# 8iPanelLED.net
KiCad netlist of a schematic drawn in EAGLE
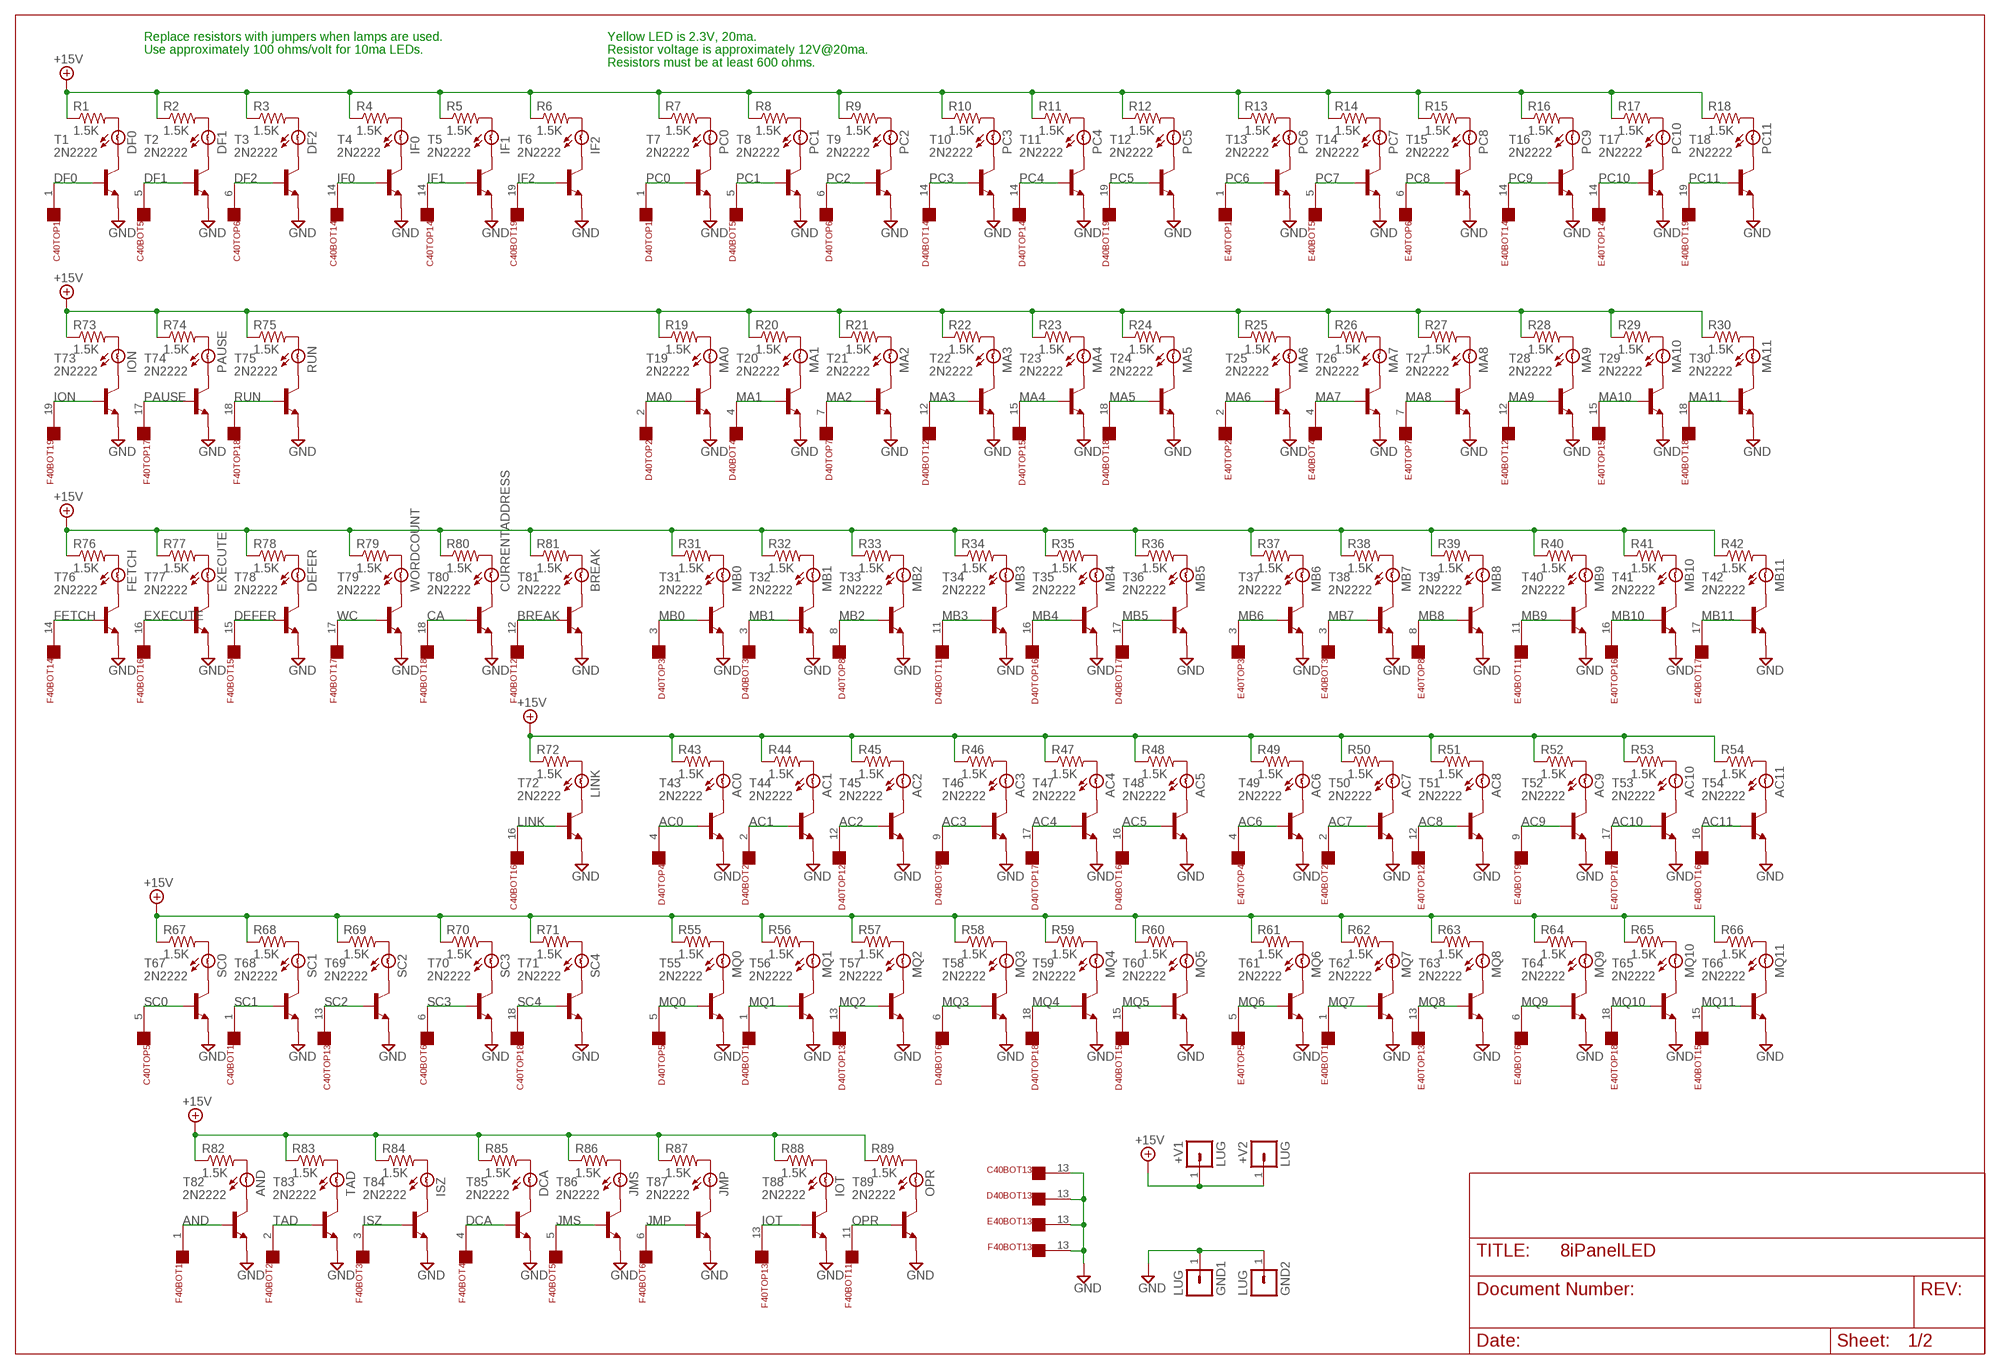
[diagram p0: schematic, sheet 1]
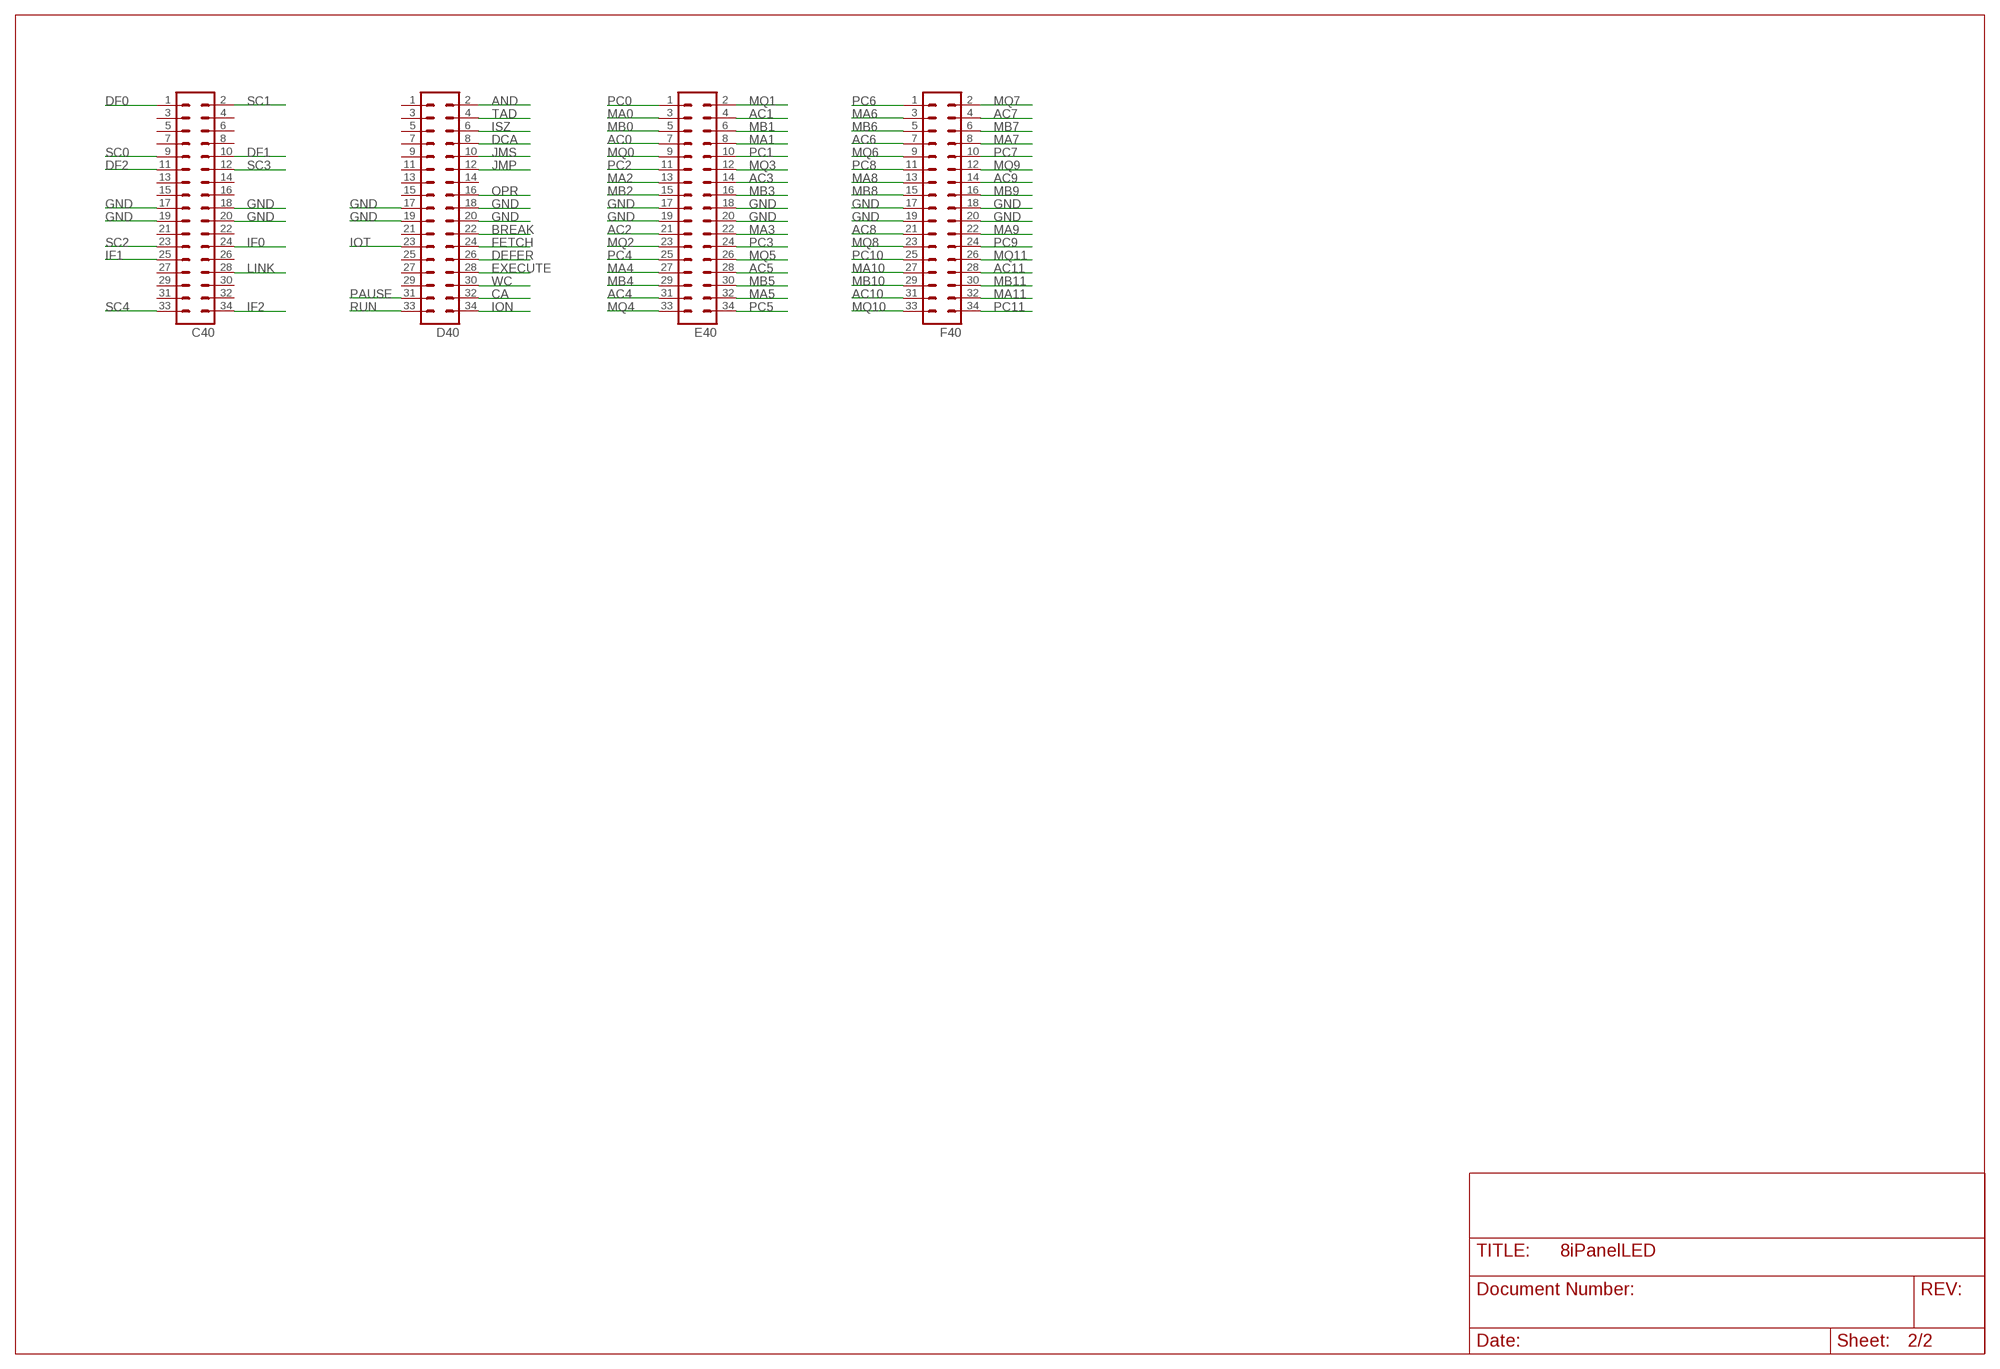
[diagram p1: schematic, sheet 2]

(export (version "E")
  (design (tool "Eeschema 10.0.6"))
  (components
    (comp (ref "C40")
      (value "MA17-2")
      (footprint "eagle-import:MA17-2")
      (libsource (lib "eagle-import") (part "MA17-2"))
    )
    (comp (ref "D40")
      (value "MA17-2")
      (footprint "eagle-import:MA17-2")
      (libsource (lib "eagle-import") (part "MA17-2"))
    )
    (comp (ref "E40")
      (value "MA17-2")
      (footprint "eagle-import:MA17-2")
      (libsource (lib "eagle-import") (part "MA17-2"))
    )
    (comp (ref "F40")
      (value "MA17-2")
      (footprint "eagle-import:MA17-2")
      (libsource (lib "eagle-import") (part "MA17-2"))
    )
    (comp (ref "+V1")
      (value "LUG")
      (footprint "eagle-import:SPADELUG")
      (libsource (lib "eagle-import") (part "LUG"))
    )
    (comp (ref "+V2")
      (value "LUG")
      (footprint "eagle-import:SPADELUG")
      (libsource (lib "eagle-import") (part "LUG"))
    )
    (comp (ref "AC0")
      (value "BULB")
      (footprint "eagle-import:BULB")
      (libsource (lib "eagle-import") (part "BULB"))
    )
    (comp (ref "AC1")
      (value "BULB")
      (footprint "eagle-import:BULB")
      (libsource (lib "eagle-import") (part "BULB"))
    )
    (comp (ref "AC2")
      (value "BULB")
      (footprint "eagle-import:BULB")
      (libsource (lib "eagle-import") (part "BULB"))
    )
    (comp (ref "AC3")
      (value "BULB")
      (footprint "eagle-import:BULB")
      (libsource (lib "eagle-import") (part "BULB"))
    )
    (comp (ref "AC4")
      (value "BULB")
      (footprint "eagle-import:BULB")
      (libsource (lib "eagle-import") (part "BULB"))
    )
    (comp (ref "AC5")
      (value "BULB")
      (footprint "eagle-import:BULB")
      (libsource (lib "eagle-import") (part "BULB"))
    )
    (comp (ref "AC6")
      (value "BULB")
      (footprint "eagle-import:BULB")
      (libsource (lib "eagle-import") (part "BULB"))
    )
    (comp (ref "AC7")
      (value "BULB")
      (footprint "eagle-import:BULB")
      (libsource (lib "eagle-import") (part "BULB"))
    )
    (comp (ref "AC8")
      (value "BULB")
      (footprint "eagle-import:BULB")
      (libsource (lib "eagle-import") (part "BULB"))
    )
    (comp (ref "AC9")
      (value "BULB")
      (footprint "eagle-import:BULB")
      (libsource (lib "eagle-import") (part "BULB"))
    )
    (comp (ref "AC10")
      (value "BULB")
      (footprint "eagle-import:BULB")
      (libsource (lib "eagle-import") (part "BULB"))
    )
    (comp (ref "AC11")
      (value "BULB")
      (footprint "eagle-import:BULB")
      (libsource (lib "eagle-import") (part "BULB"))
    )
    (comp (ref "AND")
      (value "BULB")
      (footprint "eagle-import:BULB")
      (libsource (lib "eagle-import") (part "BULB"))
    )
    (comp (ref "BREAK")
      (value "BULB")
      (footprint "eagle-import:BULB")
      (libsource (lib "eagle-import") (part "BULB"))
    )
    (comp (ref "C40BOT")
      (value "FLEX19")
      (footprint "eagle-import:FLEX19")
      (libsource (lib "eagle-import") (part "FLEX19"))
    )
    (comp (ref "C40TOP")
      (value "FLEX19")
      (footprint "eagle-import:FLEX19")
      (libsource (lib "eagle-import") (part "FLEX19"))
    )
    (comp (ref "CURRENTADDRESS")
      (value "BULB")
      (footprint "eagle-import:BULB")
      (libsource (lib "eagle-import") (part "BULB"))
    )
    (comp (ref "D40BOT")
      (value "FLEX19")
      (footprint "eagle-import:FLEX19")
      (libsource (lib "eagle-import") (part "FLEX19"))
    )
    (comp (ref "D40TOP")
      (value "FLEX19")
      (footprint "eagle-import:FLEX19")
      (libsource (lib "eagle-import") (part "FLEX19"))
    )
    (comp (ref "DCA")
      (value "BULB")
      (footprint "eagle-import:BULB")
      (libsource (lib "eagle-import") (part "BULB"))
    )
    (comp (ref "DEFER")
      (value "BULB")
      (footprint "eagle-import:BULB")
      (libsource (lib "eagle-import") (part "BULB"))
    )
    (comp (ref "DF0")
      (value "BULB")
      (footprint "eagle-import:BULB")
      (libsource (lib "eagle-import") (part "BULB"))
    )
    (comp (ref "DF1")
      (value "BULB")
      (footprint "eagle-import:BULB")
      (libsource (lib "eagle-import") (part "BULB"))
    )
    (comp (ref "DF2")
      (value "BULB")
      (footprint "eagle-import:BULB")
      (libsource (lib "eagle-import") (part "BULB"))
    )
    (comp (ref "E40BOT")
      (value "FLEX19")
      (footprint "eagle-import:FLEX19")
      (libsource (lib "eagle-import") (part "FLEX19"))
    )
    (comp (ref "E40TOP")
      (value "FLEX19")
      (footprint "eagle-import:FLEX19")
      (libsource (lib "eagle-import") (part "FLEX19"))
    )
    (comp (ref "EXECUTE")
      (value "BULB")
      (footprint "eagle-import:BULB")
      (libsource (lib "eagle-import") (part "BULB"))
    )
    (comp (ref "F40BOT")
      (value "FLEX19")
      (footprint "eagle-import:FLEX19")
      (libsource (lib "eagle-import") (part "FLEX19"))
    )
    (comp (ref "F40TOP")
      (value "FLEX19")
      (footprint "eagle-import:FLEX19")
      (libsource (lib "eagle-import") (part "FLEX19"))
    )
    (comp (ref "FETCH")
      (value "BULB")
      (footprint "eagle-import:BULB")
      (libsource (lib "eagle-import") (part "BULB"))
    )
    (comp (ref "GND1")
      (value "LUG")
      (footprint "eagle-import:SPADELUG")
      (libsource (lib "eagle-import") (part "LUG"))
    )
    (comp (ref "GND2")
      (value "LUG")
      (footprint "eagle-import:SPADELUG")
      (libsource (lib "eagle-import") (part "LUG"))
    )
    (comp (ref "IF0")
      (value "BULB")
      (footprint "eagle-import:BULB")
      (libsource (lib "eagle-import") (part "BULB"))
    )
    (comp (ref "IF1")
      (value "BULB")
      (footprint "eagle-import:BULB")
      (libsource (lib "eagle-import") (part "BULB"))
    )
    (comp (ref "IF2")
      (value "BULB")
      (footprint "eagle-import:BULB")
      (libsource (lib "eagle-import") (part "BULB"))
    )
    (comp (ref "ION")
      (value "BULB")
      (footprint "eagle-import:BULB")
      (libsource (lib "eagle-import") (part "BULB"))
    )
    (comp (ref "IOT")
      (value "BULB")
      (footprint "eagle-import:BULB")
      (libsource (lib "eagle-import") (part "BULB"))
    )
    (comp (ref "ISZ")
      (value "BULB")
      (footprint "eagle-import:BULB")
      (libsource (lib "eagle-import") (part "BULB"))
    )
    (comp (ref "JMP")
      (value "BULB")
      (footprint "eagle-import:BULB")
      (libsource (lib "eagle-import") (part "BULB"))
    )
    (comp (ref "JMS")
      (value "BULB")
      (footprint "eagle-import:BULB")
      (libsource (lib "eagle-import") (part "BULB"))
    )
    (comp (ref "LINK")
      (value "BULB")
      (footprint "eagle-import:BULB")
      (libsource (lib "eagle-import") (part "BULB"))
    )
    (comp (ref "MA0")
      (value "BULB")
      (footprint "eagle-import:BULB")
      (libsource (lib "eagle-import") (part "BULB"))
    )
    (comp (ref "MA1")
      (value "BULB")
      (footprint "eagle-import:BULB")
      (libsource (lib "eagle-import") (part "BULB"))
    )
    (comp (ref "MA2")
      (value "BULB")
      (footprint "eagle-import:BULB")
      (libsource (lib "eagle-import") (part "BULB"))
    )
    (comp (ref "MA3")
      (value "BULB")
      (footprint "eagle-import:BULB")
      (libsource (lib "eagle-import") (part "BULB"))
    )
    (comp (ref "MA4")
      (value "BULB")
      (footprint "eagle-import:BULB")
      (libsource (lib "eagle-import") (part "BULB"))
    )
    (comp (ref "MA5")
      (value "BULB")
      (footprint "eagle-import:BULB")
      (libsource (lib "eagle-import") (part "BULB"))
    )
    (comp (ref "MA6")
      (value "BULB")
      (footprint "eagle-import:BULB")
      (libsource (lib "eagle-import") (part "BULB"))
    )
    (comp (ref "MA7")
      (value "BULB")
      (footprint "eagle-import:BULB")
      (libsource (lib "eagle-import") (part "BULB"))
    )
    (comp (ref "MA8")
      (value "BULB")
      (footprint "eagle-import:BULB")
      (libsource (lib "eagle-import") (part "BULB"))
    )
    (comp (ref "MA9")
      (value "BULB")
      (footprint "eagle-import:BULB")
      (libsource (lib "eagle-import") (part "BULB"))
    )
    (comp (ref "MA10")
      (value "BULB")
      (footprint "eagle-import:BULB")
      (libsource (lib "eagle-import") (part "BULB"))
    )
    (comp (ref "MA11")
      (value "BULB")
      (footprint "eagle-import:BULB")
      (libsource (lib "eagle-import") (part "BULB"))
    )
    (comp (ref "MB0")
      (value "BULB")
      (footprint "eagle-import:BULB")
      (libsource (lib "eagle-import") (part "BULB"))
    )
    (comp (ref "MB1")
      (value "BULB")
      (footprint "eagle-import:BULB")
      (libsource (lib "eagle-import") (part "BULB"))
    )
    (comp (ref "MB2")
      (value "BULB")
      (footprint "eagle-import:BULB")
      (libsource (lib "eagle-import") (part "BULB"))
    )
    (comp (ref "MB3")
      (value "BULB")
      (footprint "eagle-import:BULB")
      (libsource (lib "eagle-import") (part "BULB"))
    )
    (comp (ref "MB4")
      (value "BULB")
      (footprint "eagle-import:BULB")
      (libsource (lib "eagle-import") (part "BULB"))
    )
    (comp (ref "MB5")
      (value "BULB")
      (footprint "eagle-import:BULB")
      (libsource (lib "eagle-import") (part "BULB"))
    )
    (comp (ref "MB6")
      (value "BULB")
      (footprint "eagle-import:BULB")
      (libsource (lib "eagle-import") (part "BULB"))
    )
    (comp (ref "MB7")
      (value "BULB")
      (footprint "eagle-import:BULB")
      (libsource (lib "eagle-import") (part "BULB"))
    )
    (comp (ref "MB8")
      (value "BULB")
      (footprint "eagle-import:BULB")
      (libsource (lib "eagle-import") (part "BULB"))
    )
    (comp (ref "MB9")
      (value "BULB")
      (footprint "eagle-import:BULB")
      (libsource (lib "eagle-import") (part "BULB"))
    )
    (comp (ref "MB10")
      (value "BULB")
      (footprint "eagle-import:BULB")
      (libsource (lib "eagle-import") (part "BULB"))
    )
    (comp (ref "MB11")
      (value "BULB")
      (footprint "eagle-import:BULB")
      (libsource (lib "eagle-import") (part "BULB"))
    )
    (comp (ref "MQ0")
      (value "BULB")
      (footprint "eagle-import:BULB")
      (libsource (lib "eagle-import") (part "BULB"))
    )
    (comp (ref "MQ1")
      (value "BULB")
      (footprint "eagle-import:BULB")
      (libsource (lib "eagle-import") (part "BULB"))
    )
    (comp (ref "MQ2")
      (value "BULB")
      (footprint "eagle-import:BULB")
      (libsource (lib "eagle-import") (part "BULB"))
    )
    (comp (ref "MQ3")
      (value "BULB")
      (footprint "eagle-import:BULB")
      (libsource (lib "eagle-import") (part "BULB"))
    )
    (comp (ref "MQ4")
      (value "BULB")
      (footprint "eagle-import:BULB")
      (libsource (lib "eagle-import") (part "BULB"))
    )
    (comp (ref "MQ5")
      (value "BULB")
      (footprint "eagle-import:BULB")
      (libsource (lib "eagle-import") (part "BULB"))
    )
    (comp (ref "MQ6")
      (value "BULB")
      (footprint "eagle-import:BULB")
      (libsource (lib "eagle-import") (part "BULB"))
    )
    (comp (ref "MQ7")
      (value "BULB")
      (footprint "eagle-import:BULB")
      (libsource (lib "eagle-import") (part "BULB"))
    )
    (comp (ref "MQ8")
      (value "BULB")
      (footprint "eagle-import:BULB")
      (libsource (lib "eagle-import") (part "BULB"))
    )
    (comp (ref "MQ9")
      (value "BULB")
      (footprint "eagle-import:BULB")
      (libsource (lib "eagle-import") (part "BULB"))
    )
    (comp (ref "MQ10")
      (value "BULB")
      (footprint "eagle-import:BULB")
      (libsource (lib "eagle-import") (part "BULB"))
    )
    (comp (ref "MQ11")
      (value "BULB")
      (footprint "eagle-import:BULB")
      (libsource (lib "eagle-import") (part "BULB"))
    )
    (comp (ref "OPR")
      (value "BULB")
      (footprint "eagle-import:BULB")
      (libsource (lib "eagle-import") (part "BULB"))
    )
    (comp (ref "PAUSE")
      (value "BULB")
      (footprint "eagle-import:BULB")
      (libsource (lib "eagle-import") (part "BULB"))
    )
    (comp (ref "PC0")
      (value "BULB")
      (footprint "eagle-import:BULB")
      (libsource (lib "eagle-import") (part "BULB"))
    )
    (comp (ref "PC1")
      (value "BULB")
      (footprint "eagle-import:BULB")
      (libsource (lib "eagle-import") (part "BULB"))
    )
    (comp (ref "PC2")
      (value "BULB")
      (footprint "eagle-import:BULB")
      (libsource (lib "eagle-import") (part "BULB"))
    )
    (comp (ref "PC3")
      (value "BULB")
      (footprint "eagle-import:BULB")
      (libsource (lib "eagle-import") (part "BULB"))
    )
    (comp (ref "PC4")
      (value "BULB")
      (footprint "eagle-import:BULB")
      (libsource (lib "eagle-import") (part "BULB"))
    )
    (comp (ref "PC5")
      (value "BULB")
      (footprint "eagle-import:BULB")
      (libsource (lib "eagle-import") (part "BULB"))
    )
    (comp (ref "PC6")
      (value "BULB")
      (footprint "eagle-import:BULB")
      (libsource (lib "eagle-import") (part "BULB"))
    )
    (comp (ref "PC7")
      (value "BULB")
      (footprint "eagle-import:BULB")
      (libsource (lib "eagle-import") (part "BULB"))
    )
    (comp (ref "PC8")
      (value "BULB")
      (footprint "eagle-import:BULB")
      (libsource (lib "eagle-import") (part "BULB"))
    )
    (comp (ref "PC9")
      (value "BULB")
      (footprint "eagle-import:BULB")
      (libsource (lib "eagle-import") (part "BULB"))
    )
    (comp (ref "PC10")
      (value "BULB")
      (footprint "eagle-import:BULB")
      (libsource (lib "eagle-import") (part "BULB"))
    )
    (comp (ref "PC11")
      (value "BULB")
      (footprint "eagle-import:BULB")
      (libsource (lib "eagle-import") (part "BULB"))
    )
    (comp (ref "R1")
      (value "1.5K")
      (footprint "eagle-import:0207_10")
      (libsource (lib "eagle-import") (part "R-US_0207/10"))
    )
    (comp (ref "R2")
      (value "1.5K")
      (footprint "eagle-import:0207_10")
      (libsource (lib "eagle-import") (part "R-US_0207/10"))
    )
    (comp (ref "R3")
      (value "1.5K")
      (footprint "eagle-import:0207_10")
      (libsource (lib "eagle-import") (part "R-US_0207/10"))
    )
    (comp (ref "R4")
      (value "1.5K")
      (footprint "eagle-import:0207_10")
      (libsource (lib "eagle-import") (part "R-US_0207/10"))
    )
    (comp (ref "R5")
      (value "1.5K")
      (footprint "eagle-import:0207_10")
      (libsource (lib "eagle-import") (part "R-US_0207/10"))
    )
    (comp (ref "R6")
      (value "1.5K")
      (footprint "eagle-import:0207_10")
      (libsource (lib "eagle-import") (part "R-US_0207/10"))
    )
    (comp (ref "R7")
      (value "1.5K")
      (footprint "eagle-import:0207_10")
      (libsource (lib "eagle-import") (part "R-US_0207/10"))
    )
    (comp (ref "R8")
      (value "1.5K")
      (footprint "eagle-import:0207_10")
      (libsource (lib "eagle-import") (part "R-US_0207/10"))
    )
    (comp (ref "R9")
      (value "1.5K")
      (footprint "eagle-import:0207_10")
      (libsource (lib "eagle-import") (part "R-US_0207/10"))
    )
    (comp (ref "R10")
      (value "1.5K")
      (footprint "eagle-import:0207_10")
      (libsource (lib "eagle-import") (part "R-US_0207/10"))
    )
    (comp (ref "R11")
      (value "1.5K")
      (footprint "eagle-import:0207_10")
      (libsource (lib "eagle-import") (part "R-US_0207/10"))
    )
    (comp (ref "R12")
      (value "1.5K")
      (footprint "eagle-import:0207_10")
      (libsource (lib "eagle-import") (part "R-US_0207/10"))
    )
    (comp (ref "R13")
      (value "1.5K")
      (footprint "eagle-import:0207_10")
      (libsource (lib "eagle-import") (part "R-US_0207/10"))
    )
    (comp (ref "R14")
      (value "1.5K")
      (footprint "eagle-import:0207_10")
      (libsource (lib "eagle-import") (part "R-US_0207/10"))
    )
    (comp (ref "R15")
      (value "1.5K")
      (footprint "eagle-import:0207_10")
      (libsource (lib "eagle-import") (part "R-US_0207/10"))
    )
    (comp (ref "R16")
      (value "1.5K")
      (footprint "eagle-import:0207_10")
      (libsource (lib "eagle-import") (part "R-US_0207/10"))
    )
    (comp (ref "R17")
      (value "1.5K")
      (footprint "eagle-import:0207_10")
      (libsource (lib "eagle-import") (part "R-US_0207/10"))
    )
    (comp (ref "R18")
      (value "1.5K")
      (footprint "eagle-import:0207_10")
      (libsource (lib "eagle-import") (part "R-US_0207/10"))
    )
    (comp (ref "R19")
      (value "1.5K")
      (footprint "eagle-import:0207_10")
      (libsource (lib "eagle-import") (part "R-US_0207/10"))
    )
    (comp (ref "R20")
      (value "1.5K")
      (footprint "eagle-import:0207_10")
      (libsource (lib "eagle-import") (part "R-US_0207/10"))
    )
    (comp (ref "R21")
      (value "1.5K")
      (footprint "eagle-import:0207_10")
      (libsource (lib "eagle-import") (part "R-US_0207/10"))
    )
    (comp (ref "R22")
      (value "1.5K")
      (footprint "eagle-import:0207_10")
      (libsource (lib "eagle-import") (part "R-US_0207/10"))
    )
    (comp (ref "R23")
      (value "1.5K")
      (footprint "eagle-import:0207_10")
      (libsource (lib "eagle-import") (part "R-US_0207/10"))
    )
    (comp (ref "R24")
      (value "1.5K")
      (footprint "eagle-import:0207_10")
      (libsource (lib "eagle-import") (part "R-US_0207/10"))
    )
    (comp (ref "R25")
      (value "1.5K")
      (footprint "eagle-import:0207_10")
      (libsource (lib "eagle-import") (part "R-US_0207/10"))
    )
    (comp (ref "R26")
      (value "1.5K")
      (footprint "eagle-import:0207_10")
      (libsource (lib "eagle-import") (part "R-US_0207/10"))
    )
    (comp (ref "R27")
      (value "1.5K")
      (footprint "eagle-import:0207_10")
      (libsource (lib "eagle-import") (part "R-US_0207/10"))
    )
    (comp (ref "R28")
      (value "1.5K")
      (footprint "eagle-import:0207_10")
      (libsource (lib "eagle-import") (part "R-US_0207/10"))
    )
    (comp (ref "R29")
      (value "1.5K")
      (footprint "eagle-import:0207_10")
      (libsource (lib "eagle-import") (part "R-US_0207/10"))
    )
    (comp (ref "R30")
      (value "1.5K")
      (footprint "eagle-import:0207_10")
      (libsource (lib "eagle-import") (part "R-US_0207/10"))
    )
    (comp (ref "R31")
      (value "1.5K")
      (footprint "eagle-import:0207_10")
      (libsource (lib "eagle-import") (part "R-US_0207/10"))
    )
    (comp (ref "R32")
      (value "1.5K")
      (footprint "eagle-import:0207_10")
      (libsource (lib "eagle-import") (part "R-US_0207/10"))
    )
    (comp (ref "R33")
      (value "1.5K")
      (footprint "eagle-import:0207_10")
      (libsource (lib "eagle-import") (part "R-US_0207/10"))
    )
    (comp (ref "R34")
      (value "1.5K")
      (footprint "eagle-import:0207_10")
      (libsource (lib "eagle-import") (part "R-US_0207/10"))
    )
    (comp (ref "R35")
      (value "1.5K")
      (footprint "eagle-import:0207_10")
      (libsource (lib "eagle-import") (part "R-US_0207/10"))
    )
    (comp (ref "R36")
      (value "1.5K")
      (footprint "eagle-import:0207_10")
      (libsource (lib "eagle-import") (part "R-US_0207/10"))
    )
    (comp (ref "R37")
      (value "1.5K")
      (footprint "eagle-import:0207_10")
      (libsource (lib "eagle-import") (part "R-US_0207/10"))
    )
    (comp (ref "R38")
      (value "1.5K")
      (footprint "eagle-import:0207_10")
      (libsource (lib "eagle-import") (part "R-US_0207/10"))
    )
    (comp (ref "R39")
      (value "1.5K")
      (footprint "eagle-import:0207_10")
      (libsource (lib "eagle-import") (part "R-US_0207/10"))
    )
    (comp (ref "R40")
      (value "1.5K")
      (footprint "eagle-import:0207_10")
      (libsource (lib "eagle-import") (part "R-US_0207/10"))
    )
    (comp (ref "R41")
      (value "1.5K")
      (footprint "eagle-import:0207_10")
      (libsource (lib "eagle-import") (part "R-US_0207/10"))
    )
    (comp (ref "R42")
      (value "1.5K")
      (footprint "eagle-import:0207_10")
      (libsource (lib "eagle-import") (part "R-US_0207/10"))
    )
    (comp (ref "R43")
      (value "1.5K")
      (footprint "eagle-import:0207_10")
      (libsource (lib "eagle-import") (part "R-US_0207/10"))
    )
    (comp (ref "R44")
      (value "1.5K")
      (footprint "eagle-import:0207_10")
      (libsource (lib "eagle-import") (part "R-US_0207/10"))
    )
    (comp (ref "R45")
      (value "1.5K")
      (footprint "eagle-import:0207_10")
      (libsource (lib "eagle-import") (part "R-US_0207/10"))
    )
    (comp (ref "R46")
      (value "1.5K")
      (footprint "eagle-import:0207_10")
      (libsource (lib "eagle-import") (part "R-US_0207/10"))
    )
    (comp (ref "R47")
      (value "1.5K")
      (footprint "eagle-import:0207_10")
      (libsource (lib "eagle-import") (part "R-US_0207/10"))
    )
    (comp (ref "R48")
      (value "1.5K")
      (footprint "eagle-import:0207_10")
      (libsource (lib "eagle-import") (part "R-US_0207/10"))
    )
    (comp (ref "R49")
      (value "1.5K")
      (footprint "eagle-import:0207_10")
      (libsource (lib "eagle-import") (part "R-US_0207/10"))
    )
    (comp (ref "R50")
      (value "1.5K")
      (footprint "eagle-import:0207_10")
      (libsource (lib "eagle-import") (part "R-US_0207/10"))
    )
    (comp (ref "R51")
      (value "1.5K")
      (footprint "eagle-import:0207_10")
      (libsource (lib "eagle-import") (part "R-US_0207/10"))
    )
    (comp (ref "R52")
      (value "1.5K")
      (footprint "eagle-import:0207_10")
      (libsource (lib "eagle-import") (part "R-US_0207/10"))
    )
    (comp (ref "R53")
      (value "1.5K")
      (footprint "eagle-import:0207_10")
      (libsource (lib "eagle-import") (part "R-US_0207/10"))
    )
    (comp (ref "R54")
      (value "1.5K")
      (footprint "eagle-import:0207_10")
      (libsource (lib "eagle-import") (part "R-US_0207/10"))
    )
    (comp (ref "R55")
      (value "1.5K")
      (footprint "eagle-import:0207_10")
      (libsource (lib "eagle-import") (part "R-US_0207/10"))
    )
    (comp (ref "R56")
      (value "1.5K")
      (footprint "eagle-import:0207_10")
      (libsource (lib "eagle-import") (part "R-US_0207/10"))
    )
    (comp (ref "R57")
      (value "1.5K")
      (footprint "eagle-import:0207_10")
      (libsource (lib "eagle-import") (part "R-US_0207/10"))
    )
    (comp (ref "R58")
      (value "1.5K")
      (footprint "eagle-import:0207_10")
      (libsource (lib "eagle-import") (part "R-US_0207/10"))
    )
    (comp (ref "R59")
      (value "1.5K")
      (footprint "eagle-import:0207_10")
      (libsource (lib "eagle-import") (part "R-US_0207/10"))
    )
    (comp (ref "R60")
      (value "1.5K")
      (footprint "eagle-import:0207_10")
      (libsource (lib "eagle-import") (part "R-US_0207/10"))
    )
    (comp (ref "R61")
      (value "1.5K")
      (footprint "eagle-import:0207_10")
      (libsource (lib "eagle-import") (part "R-US_0207/10"))
    )
    (comp (ref "R62")
      (value "1.5K")
      (footprint "eagle-import:0207_10")
      (libsource (lib "eagle-import") (part "R-US_0207/10"))
    )
    (comp (ref "R63")
      (value "1.5K")
      (footprint "eagle-import:0207_10")
      (libsource (lib "eagle-import") (part "R-US_0207/10"))
    )
    (comp (ref "R64")
      (value "1.5K")
      (footprint "eagle-import:0207_10")
      (libsource (lib "eagle-import") (part "R-US_0207/10"))
    )
    (comp (ref "R65")
      (value "1.5K")
      (footprint "eagle-import:0207_10")
      (libsource (lib "eagle-import") (part "R-US_0207/10"))
    )
    (comp (ref "R66")
      (value "1.5K")
      (footprint "eagle-import:0207_10")
      (libsource (lib "eagle-import") (part "R-US_0207/10"))
    )
    (comp (ref "R67")
      (value "1.5K")
      (footprint "eagle-import:0207_10")
      (libsource (lib "eagle-import") (part "R-US_0207/10"))
    )
    (comp (ref "R68")
      (value "1.5K")
      (footprint "eagle-import:0207_10")
      (libsource (lib "eagle-import") (part "R-US_0207/10"))
    )
    (comp (ref "R69")
      (value "1.5K")
      (footprint "eagle-import:0207_10")
      (libsource (lib "eagle-import") (part "R-US_0207/10"))
    )
    (comp (ref "R70")
      (value "1.5K")
      (footprint "eagle-import:0207_10")
      (libsource (lib "eagle-import") (part "R-US_0207/10"))
    )
    (comp (ref "R71")
      (value "1.5K")
      (footprint "eagle-import:0207_10")
      (libsource (lib "eagle-import") (part "R-US_0207/10"))
    )
    (comp (ref "R72")
      (value "1.5K")
      (footprint "eagle-import:0207_10")
      (libsource (lib "eagle-import") (part "R-US_0207/10"))
    )
    (comp (ref "R73")
      (value "1.5K")
      (footprint "eagle-import:0207_10")
      (libsource (lib "eagle-import") (part "R-US_0207/10"))
    )
    (comp (ref "R74")
      (value "1.5K")
      (footprint "eagle-import:0207_10")
      (libsource (lib "eagle-import") (part "R-US_0207/10"))
    )
    (comp (ref "R75")
      (value "1.5K")
      (footprint "eagle-import:0207_10")
      (libsource (lib "eagle-import") (part "R-US_0207/10"))
    )
    (comp (ref "R76")
      (value "1.5K")
      (footprint "eagle-import:0207_10")
      (libsource (lib "eagle-import") (part "R-US_0207/10"))
    )
    (comp (ref "R77")
      (value "1.5K")
      (footprint "eagle-import:0207_10")
      (libsource (lib "eagle-import") (part "R-US_0207/10"))
    )
    (comp (ref "R78")
      (value "1.5K")
      (footprint "eagle-import:0207_10")
      (libsource (lib "eagle-import") (part "R-US_0207/10"))
    )
    (comp (ref "R79")
      (value "1.5K")
      (footprint "eagle-import:0207_10")
      (libsource (lib "eagle-import") (part "R-US_0207/10"))
    )
    (comp (ref "R80")
      (value "1.5K")
      (footprint "eagle-import:0207_10")
      (libsource (lib "eagle-import") (part "R-US_0207/10"))
    )
    (comp (ref "R81")
      (value "1.5K")
      (footprint "eagle-import:0207_10")
      (libsource (lib "eagle-import") (part "R-US_0207/10"))
    )
    (comp (ref "R82")
      (value "1.5K")
      (footprint "eagle-import:0207_10")
      (libsource (lib "eagle-import") (part "R-US_0207/10"))
    )
    (comp (ref "R83")
      (value "1.5K")
      (footprint "eagle-import:0207_10")
      (libsource (lib "eagle-import") (part "R-US_0207/10"))
    )
    (comp (ref "R84")
      (value "1.5K")
      (footprint "eagle-import:0207_10")
      (libsource (lib "eagle-import") (part "R-US_0207/10"))
    )
    (comp (ref "R85")
      (value "1.5K")
      (footprint "eagle-import:0207_10")
      (libsource (lib "eagle-import") (part "R-US_0207/10"))
    )
    (comp (ref "R86")
      (value "1.5K")
      (footprint "eagle-import:0207_10")
      (libsource (lib "eagle-import") (part "R-US_0207/10"))
    )
    (comp (ref "R87")
      (value "1.5K")
      (footprint "eagle-import:0207_10")
      (libsource (lib "eagle-import") (part "R-US_0207/10"))
    )
    (comp (ref "R88")
      (value "1.5K")
      (footprint "eagle-import:0207_10")
      (libsource (lib "eagle-import") (part "R-US_0207/10"))
    )
    (comp (ref "R89")
      (value "1.5K")
      (footprint "eagle-import:0207_10")
      (libsource (lib "eagle-import") (part "R-US_0207/10"))
    )
    (comp (ref "RUN")
      (value "BULB")
      (footprint "eagle-import:BULB")
      (libsource (lib "eagle-import") (part "BULB"))
    )
    (comp (ref "SC0")
      (value "BULB")
      (footprint "eagle-import:BULB")
      (libsource (lib "eagle-import") (part "BULB"))
    )
    (comp (ref "SC1")
      (value "BULB")
      (footprint "eagle-import:BULB")
      (libsource (lib "eagle-import") (part "BULB"))
    )
    (comp (ref "SC2")
      (value "BULB")
      (footprint "eagle-import:BULB")
      (libsource (lib "eagle-import") (part "BULB"))
    )
    (comp (ref "SC3")
      (value "BULB")
      (footprint "eagle-import:BULB")
      (libsource (lib "eagle-import") (part "BULB"))
    )
    (comp (ref "SC4")
      (value "BULB")
      (footprint "eagle-import:BULB")
      (libsource (lib "eagle-import") (part "BULB"))
    )
    (comp (ref "T1")
      (value "2N2222")
      (footprint "eagle-import:TO92")
      (libsource (lib "eagle-import") (part "-NPN-TO92"))
    )
    (comp (ref "T2")
      (value "2N2222")
      (footprint "eagle-import:TO92")
      (libsource (lib "eagle-import") (part "-NPN-TO92"))
    )
    (comp (ref "T3")
      (value "2N2222")
      (footprint "eagle-import:TO92")
      (libsource (lib "eagle-import") (part "-NPN-TO92"))
    )
    (comp (ref "T4")
      (value "2N2222")
      (footprint "eagle-import:TO92")
      (libsource (lib "eagle-import") (part "-NPN-TO92"))
    )
    (comp (ref "T5")
      (value "2N2222")
      (footprint "eagle-import:TO92")
      (libsource (lib "eagle-import") (part "-NPN-TO92"))
    )
    (comp (ref "T6")
      (value "2N2222")
      (footprint "eagle-import:TO92")
      (libsource (lib "eagle-import") (part "-NPN-TO92"))
    )
    (comp (ref "T7")
      (value "2N2222")
      (footprint "eagle-import:TO92")
      (libsource (lib "eagle-import") (part "-NPN-TO92"))
    )
    (comp (ref "T8")
      (value "2N2222")
      (footprint "eagle-import:TO92")
      (libsource (lib "eagle-import") (part "-NPN-TO92"))
    )
    (comp (ref "T9")
      (value "2N2222")
      (footprint "eagle-import:TO92")
      (libsource (lib "eagle-import") (part "-NPN-TO92"))
    )
    (comp (ref "T10")
      (value "2N2222")
      (footprint "eagle-import:TO92")
      (libsource (lib "eagle-import") (part "-NPN-TO92"))
    )
    (comp (ref "T11")
      (value "2N2222")
      (footprint "eagle-import:TO92")
      (libsource (lib "eagle-import") (part "-NPN-TO92"))
    )
    (comp (ref "T12")
      (value "2N2222")
      (footprint "eagle-import:TO92")
      (libsource (lib "eagle-import") (part "-NPN-TO92"))
    )
    (comp (ref "T13")
      (value "2N2222")
      (footprint "eagle-import:TO92")
      (libsource (lib "eagle-import") (part "-NPN-TO92"))
    )
    (comp (ref "T14")
      (value "2N2222")
      (footprint "eagle-import:TO92")
      (libsource (lib "eagle-import") (part "-NPN-TO92"))
    )
    (comp (ref "T15")
      (value "2N2222")
      (footprint "eagle-import:TO92")
      (libsource (lib "eagle-import") (part "-NPN-TO92"))
    )
    (comp (ref "T16")
      (value "2N2222")
      (footprint "eagle-import:TO92")
      (libsource (lib "eagle-import") (part "-NPN-TO92"))
    )
    (comp (ref "T17")
      (value "2N2222")
      (footprint "eagle-import:TO92")
      (libsource (lib "eagle-import") (part "-NPN-TO92"))
    )
    (comp (ref "T18")
      (value "2N2222")
      (footprint "eagle-import:TO92")
      (libsource (lib "eagle-import") (part "-NPN-TO92"))
    )
    (comp (ref "T19")
      (value "2N2222")
      (footprint "eagle-import:TO92")
      (libsource (lib "eagle-import") (part "-NPN-TO92"))
    )
    (comp (ref "T20")
      (value "2N2222")
      (footprint "eagle-import:TO92")
      (libsource (lib "eagle-import") (part "-NPN-TO92"))
    )
    (comp (ref "T21")
      (value "2N2222")
      (footprint "eagle-import:TO92")
      (libsource (lib "eagle-import") (part "-NPN-TO92"))
    )
    (comp (ref "T22")
      (value "2N2222")
      (footprint "eagle-import:TO92")
      (libsource (lib "eagle-import") (part "-NPN-TO92"))
    )
    (comp (ref "T23")
      (value "2N2222")
      (footprint "eagle-import:TO92")
      (libsource (lib "eagle-import") (part "-NPN-TO92"))
    )
    (comp (ref "T24")
      (value "2N2222")
      (footprint "eagle-import:TO92")
      (libsource (lib "eagle-import") (part "-NPN-TO92"))
    )
    (comp (ref "T25")
      (value "2N2222")
      (footprint "eagle-import:TO92")
      (libsource (lib "eagle-import") (part "-NPN-TO92"))
    )
    (comp (ref "T26")
      (value "2N2222")
      (footprint "eagle-import:TO92")
      (libsource (lib "eagle-import") (part "-NPN-TO92"))
    )
    (comp (ref "T27")
      (value "2N2222")
      (footprint "eagle-import:TO92")
      (libsource (lib "eagle-import") (part "-NPN-TO92"))
    )
    (comp (ref "T28")
      (value "2N2222")
      (footprint "eagle-import:TO92")
      (libsource (lib "eagle-import") (part "-NPN-TO92"))
    )
    (comp (ref "T29")
      (value "2N2222")
      (footprint "eagle-import:TO92")
      (libsource (lib "eagle-import") (part "-NPN-TO92"))
    )
    (comp (ref "T30")
      (value "2N2222")
      (footprint "eagle-import:TO92")
      (libsource (lib "eagle-import") (part "-NPN-TO92"))
    )
    (comp (ref "T31")
      (value "2N2222")
      (footprint "eagle-import:TO92")
      (libsource (lib "eagle-import") (part "-NPN-TO92"))
    )
    (comp (ref "T32")
      (value "2N2222")
      (footprint "eagle-import:TO92")
      (libsource (lib "eagle-import") (part "-NPN-TO92"))
    )
    (comp (ref "T33")
      (value "2N2222")
      (footprint "eagle-import:TO92")
      (libsource (lib "eagle-import") (part "-NPN-TO92"))
    )
    (comp (ref "T34")
      (value "2N2222")
      (footprint "eagle-import:TO92")
      (libsource (lib "eagle-import") (part "-NPN-TO92"))
    )
    (comp (ref "T35")
      (value "2N2222")
      (footprint "eagle-import:TO92")
      (libsource (lib "eagle-import") (part "-NPN-TO92"))
    )
    (comp (ref "T36")
      (value "2N2222")
      (footprint "eagle-import:TO92")
      (libsource (lib "eagle-import") (part "-NPN-TO92"))
    )
    (comp (ref "T37")
      (value "2N2222")
      (footprint "eagle-import:TO92")
      (libsource (lib "eagle-import") (part "-NPN-TO92"))
    )
    (comp (ref "T38")
      (value "2N2222")
      (footprint "eagle-import:TO92")
      (libsource (lib "eagle-import") (part "-NPN-TO92"))
    )
    (comp (ref "T39")
      (value "2N2222")
      (footprint "eagle-import:TO92")
      (libsource (lib "eagle-import") (part "-NPN-TO92"))
    )
    (comp (ref "T40")
      (value "2N2222")
      (footprint "eagle-import:TO92")
      (libsource (lib "eagle-import") (part "-NPN-TO92"))
    )
    (comp (ref "T41")
      (value "2N2222")
      (footprint "eagle-import:TO92")
      (libsource (lib "eagle-import") (part "-NPN-TO92"))
    )
    (comp (ref "T42")
      (value "2N2222")
      (footprint "eagle-import:TO92")
      (libsource (lib "eagle-import") (part "-NPN-TO92"))
    )
    (comp (ref "T43")
      (value "2N2222")
      (footprint "eagle-import:TO92")
      (libsource (lib "eagle-import") (part "-NPN-TO92"))
    )
    (comp (ref "T44")
      (value "2N2222")
      (footprint "eagle-import:TO92")
      (libsource (lib "eagle-import") (part "-NPN-TO92"))
    )
    (comp (ref "T45")
      (value "2N2222")
      (footprint "eagle-import:TO92")
      (libsource (lib "eagle-import") (part "-NPN-TO92"))
    )
    (comp (ref "T46")
      (value "2N2222")
      (footprint "eagle-import:TO92")
      (libsource (lib "eagle-import") (part "-NPN-TO92"))
    )
    (comp (ref "T47")
      (value "2N2222")
      (footprint "eagle-import:TO92")
      (libsource (lib "eagle-import") (part "-NPN-TO92"))
    )
    (comp (ref "T48")
      (value "2N2222")
      (footprint "eagle-import:TO92")
      (libsource (lib "eagle-import") (part "-NPN-TO92"))
    )
    (comp (ref "T49")
      (value "2N2222")
      (footprint "eagle-import:TO92")
      (libsource (lib "eagle-import") (part "-NPN-TO92"))
    )
    (comp (ref "T50")
      (value "2N2222")
      (footprint "eagle-import:TO92")
      (libsource (lib "eagle-import") (part "-NPN-TO92"))
    )
    (comp (ref "T51")
      (value "2N2222")
      (footprint "eagle-import:TO92")
      (libsource (lib "eagle-import") (part "-NPN-TO92"))
    )
    (comp (ref "T52")
      (value "2N2222")
      (footprint "eagle-import:TO92")
      (libsource (lib "eagle-import") (part "-NPN-TO92"))
    )
    (comp (ref "T53")
      (value "2N2222")
      (footprint "eagle-import:TO92")
      (libsource (lib "eagle-import") (part "-NPN-TO92"))
    )
    (comp (ref "T54")
      (value "2N2222")
      (footprint "eagle-import:TO92")
      (libsource (lib "eagle-import") (part "-NPN-TO92"))
    )
    (comp (ref "T55")
      (value "2N2222")
      (footprint "eagle-import:TO92")
      (libsource (lib "eagle-import") (part "-NPN-TO92"))
    )
    (comp (ref "T56")
      (value "2N2222")
      (footprint "eagle-import:TO92")
      (libsource (lib "eagle-import") (part "-NPN-TO92"))
    )
    (comp (ref "T57")
      (value "2N2222")
      (footprint "eagle-import:TO92")
      (libsource (lib "eagle-import") (part "-NPN-TO92"))
    )
    (comp (ref "T58")
      (value "2N2222")
      (footprint "eagle-import:TO92")
      (libsource (lib "eagle-import") (part "-NPN-TO92"))
    )
    (comp (ref "T59")
      (value "2N2222")
      (footprint "eagle-import:TO92")
      (libsource (lib "eagle-import") (part "-NPN-TO92"))
    )
    (comp (ref "T60")
      (value "2N2222")
      (footprint "eagle-import:TO92")
      (libsource (lib "eagle-import") (part "-NPN-TO92"))
    )
    (comp (ref "T61")
      (value "2N2222")
      (footprint "eagle-import:TO92")
      (libsource (lib "eagle-import") (part "-NPN-TO92"))
    )
    (comp (ref "T62")
      (value "2N2222")
      (footprint "eagle-import:TO92")
      (libsource (lib "eagle-import") (part "-NPN-TO92"))
    )
    (comp (ref "T63")
      (value "2N2222")
      (footprint "eagle-import:TO92")
      (libsource (lib "eagle-import") (part "-NPN-TO92"))
    )
    (comp (ref "T64")
      (value "2N2222")
      (footprint "eagle-import:TO92")
      (libsource (lib "eagle-import") (part "-NPN-TO92"))
    )
    (comp (ref "T65")
      (value "2N2222")
      (footprint "eagle-import:TO92")
      (libsource (lib "eagle-import") (part "-NPN-TO92"))
    )
    (comp (ref "T66")
      (value "2N2222")
      (footprint "eagle-import:TO92")
      (libsource (lib "eagle-import") (part "-NPN-TO92"))
    )
    (comp (ref "T67")
      (value "2N2222")
      (footprint "eagle-import:TO92")
      (libsource (lib "eagle-import") (part "-NPN-TO92"))
    )
    (comp (ref "T68")
      (value "2N2222")
      (footprint "eagle-import:TO92")
      (libsource (lib "eagle-import") (part "-NPN-TO92"))
    )
    (comp (ref "T69")
      (value "2N2222")
      (footprint "eagle-import:TO92")
      (libsource (lib "eagle-import") (part "-NPN-TO92"))
    )
    (comp (ref "T70")
      (value "2N2222")
      (footprint "eagle-import:TO92")
      (libsource (lib "eagle-import") (part "-NPN-TO92"))
    )
    (comp (ref "T71")
      (value "2N2222")
      (footprint "eagle-import:TO92")
      (libsource (lib "eagle-import") (part "-NPN-TO92"))
    )
    (comp (ref "T72")
      (value "2N2222")
      (footprint "eagle-import:TO92")
      (libsource (lib "eagle-import") (part "-NPN-TO92"))
    )
    (comp (ref "T73")
      (value "2N2222")
      (footprint "eagle-import:TO92")
      (libsource (lib "eagle-import") (part "-NPN-TO92"))
    )
    (comp (ref "T74")
      (value "2N2222")
      (footprint "eagle-import:TO92")
      (libsource (lib "eagle-import") (part "-NPN-TO92"))
    )
    (comp (ref "T75")
      (value "2N2222")
      (footprint "eagle-import:TO92")
      (libsource (lib "eagle-import") (part "-NPN-TO92"))
    )
    (comp (ref "T76")
      (value "2N2222")
      (footprint "eagle-import:TO92")
      (libsource (lib "eagle-import") (part "-NPN-TO92"))
    )
    (comp (ref "T77")
      (value "2N2222")
      (footprint "eagle-import:TO92")
      (libsource (lib "eagle-import") (part "-NPN-TO92"))
    )
    (comp (ref "T78")
      (value "2N2222")
      (footprint "eagle-import:TO92")
      (libsource (lib "eagle-import") (part "-NPN-TO92"))
    )
    (comp (ref "T79")
      (value "2N2222")
      (footprint "eagle-import:TO92")
      (libsource (lib "eagle-import") (part "-NPN-TO92"))
    )
    (comp (ref "T80")
      (value "2N2222")
      (footprint "eagle-import:TO92")
      (libsource (lib "eagle-import") (part "-NPN-TO92"))
    )
    (comp (ref "T81")
      (value "2N2222")
      (footprint "eagle-import:TO92")
      (libsource (lib "eagle-import") (part "-NPN-TO92"))
    )
    (comp (ref "T82")
      (value "2N2222")
      (footprint "eagle-import:TO92")
      (libsource (lib "eagle-import") (part "-NPN-TO92"))
    )
    (comp (ref "T83")
      (value "2N2222")
      (footprint "eagle-import:TO92")
      (libsource (lib "eagle-import") (part "-NPN-TO92"))
    )
    (comp (ref "T84")
      (value "2N2222")
      (footprint "eagle-import:TO92")
      (libsource (lib "eagle-import") (part "-NPN-TO92"))
    )
    (comp (ref "T85")
      (value "2N2222")
      (footprint "eagle-import:TO92")
      (libsource (lib "eagle-import") (part "-NPN-TO92"))
    )
    (comp (ref "T86")
      (value "2N2222")
      (footprint "eagle-import:TO92")
      (libsource (lib "eagle-import") (part "-NPN-TO92"))
    )
    (comp (ref "T87")
      (value "2N2222")
      (footprint "eagle-import:TO92")
      (libsource (lib "eagle-import") (part "-NPN-TO92"))
    )
    (comp (ref "T88")
      (value "2N2222")
      (footprint "eagle-import:TO92")
      (libsource (lib "eagle-import") (part "-NPN-TO92"))
    )
    (comp (ref "T89")
      (value "2N2222")
      (footprint "eagle-import:TO92")
      (libsource (lib "eagle-import") (part "-NPN-TO92"))
    )
    (comp (ref "TAD")
      (value "BULB")
      (footprint "eagle-import:BULB")
      (libsource (lib "eagle-import") (part "BULB"))
    )
    (comp (ref "WORDCOUNT")
      (value "BULB")
      (footprint "eagle-import:BULB")
      (libsource (lib "eagle-import") (part "BULB"))
    )
  )
  (nets
    (net (code "1") (name "+15V") (class "Default")
      (node (ref "+V1") (pin "1") (pinfunction "1_1") (pintype "passive"))
      (node (ref "+V2") (pin "1") (pinfunction "1_1") (pintype "passive"))
      (node (ref "R1") (pin "1") (pinfunction "1_1") (pintype "passive"))
      (node (ref "R10") (pin "1") (pinfunction "1_1") (pintype "passive"))
      (node (ref "R11") (pin "1") (pinfunction "1_1") (pintype "passive"))
      (node (ref "R12") (pin "1") (pinfunction "1_1") (pintype "passive"))
      (node (ref "R13") (pin "1") (pinfunction "1_1") (pintype "passive"))
      (node (ref "R14") (pin "1") (pinfunction "1_1") (pintype "passive"))
      (node (ref "R15") (pin "1") (pinfunction "1_1") (pintype "passive"))
      (node (ref "R16") (pin "1") (pinfunction "1_1") (pintype "passive"))
      (node (ref "R17") (pin "1") (pinfunction "1_1") (pintype "passive"))
      (node (ref "R18") (pin "1") (pinfunction "1_1") (pintype "passive"))
      (node (ref "R19") (pin "1") (pinfunction "1_1") (pintype "passive"))
      (node (ref "R2") (pin "1") (pinfunction "1_1") (pintype "passive"))
      (node (ref "R20") (pin "1") (pinfunction "1_1") (pintype "passive"))
      (node (ref "R21") (pin "1") (pinfunction "1_1") (pintype "passive"))
      (node (ref "R22") (pin "1") (pinfunction "1_1") (pintype "passive"))
      (node (ref "R23") (pin "1") (pinfunction "1_1") (pintype "passive"))
      (node (ref "R24") (pin "1") (pinfunction "1_1") (pintype "passive"))
      (node (ref "R25") (pin "1") (pinfunction "1_1") (pintype "passive"))
      (node (ref "R26") (pin "1") (pinfunction "1_1") (pintype "passive"))
      (node (ref "R27") (pin "1") (pinfunction "1_1") (pintype "passive"))
      (node (ref "R28") (pin "1") (pinfunction "1_1") (pintype "passive"))
      (node (ref "R29") (pin "1") (pinfunction "1_1") (pintype "passive"))
      (node (ref "R3") (pin "1") (pinfunction "1_1") (pintype "passive"))
      (node (ref "R30") (pin "1") (pinfunction "1_1") (pintype "passive"))
      (node (ref "R31") (pin "1") (pinfunction "1_1") (pintype "passive"))
      (node (ref "R32") (pin "1") (pinfunction "1_1") (pintype "passive"))
      (node (ref "R33") (pin "1") (pinfunction "1_1") (pintype "passive"))
      (node (ref "R34") (pin "1") (pinfunction "1_1") (pintype "passive"))
      (node (ref "R35") (pin "1") (pinfunction "1_1") (pintype "passive"))
      (node (ref "R36") (pin "1") (pinfunction "1_1") (pintype "passive"))
      (node (ref "R37") (pin "1") (pinfunction "1_1") (pintype "passive"))
      (node (ref "R38") (pin "1") (pinfunction "1_1") (pintype "passive"))
      (node (ref "R39") (pin "1") (pinfunction "1_1") (pintype "passive"))
      (node (ref "R4") (pin "1") (pinfunction "1_1") (pintype "passive"))
      (node (ref "R40") (pin "1") (pinfunction "1_1") (pintype "passive"))
      (node (ref "R41") (pin "1") (pinfunction "1_1") (pintype "passive"))
      (node (ref "R42") (pin "1") (pinfunction "1_1") (pintype "passive"))
      (node (ref "R43") (pin "1") (pinfunction "1_1") (pintype "passive"))
      (node (ref "R44") (pin "1") (pinfunction "1_1") (pintype "passive"))
      (node (ref "R45") (pin "1") (pinfunction "1_1") (pintype "passive"))
      (node (ref "R46") (pin "1") (pinfunction "1_1") (pintype "passive"))
      (node (ref "R47") (pin "1") (pinfunction "1_1") (pintype "passive"))
      (node (ref "R48") (pin "1") (pinfunction "1_1") (pintype "passive"))
      (node (ref "R49") (pin "1") (pinfunction "1_1") (pintype "passive"))
      (node (ref "R5") (pin "1") (pinfunction "1_1") (pintype "passive"))
      (node (ref "R50") (pin "1") (pinfunction "1_1") (pintype "passive"))
      (node (ref "R51") (pin "1") (pinfunction "1_1") (pintype "passive"))
      (node (ref "R52") (pin "1") (pinfunction "1_1") (pintype "passive"))
      (node (ref "R53") (pin "1") (pinfunction "1_1") (pintype "passive"))
      (node (ref "R54") (pin "1") (pinfunction "1_1") (pintype "passive"))
      (node (ref "R55") (pin "1") (pinfunction "1_1") (pintype "passive"))
      (node (ref "R56") (pin "1") (pinfunction "1_1") (pintype "passive"))
      (node (ref "R57") (pin "1") (pinfunction "1_1") (pintype "passive"))
      (node (ref "R58") (pin "1") (pinfunction "1_1") (pintype "passive"))
      (node (ref "R59") (pin "1") (pinfunction "1_1") (pintype "passive"))
      (node (ref "R6") (pin "1") (pinfunction "1_1") (pintype "passive"))
      (node (ref "R60") (pin "1") (pinfunction "1_1") (pintype "passive"))
      (node (ref "R61") (pin "1") (pinfunction "1_1") (pintype "passive"))
      (node (ref "R62") (pin "1") (pinfunction "1_1") (pintype "passive"))
      (node (ref "R63") (pin "1") (pinfunction "1_1") (pintype "passive"))
      (node (ref "R64") (pin "1") (pinfunction "1_1") (pintype "passive"))
      (node (ref "R65") (pin "1") (pinfunction "1_1") (pintype "passive"))
      (node (ref "R66") (pin "1") (pinfunction "1_1") (pintype "passive"))
      (node (ref "R67") (pin "1") (pinfunction "1_1") (pintype "passive"))
      (node (ref "R68") (pin "1") (pinfunction "1_1") (pintype "passive"))
      (node (ref "R69") (pin "1") (pinfunction "1_1") (pintype "passive"))
      (node (ref "R7") (pin "1") (pinfunction "1_1") (pintype "passive"))
      (node (ref "R70") (pin "1") (pinfunction "1_1") (pintype "passive"))
      (node (ref "R71") (pin "1") (pinfunction "1_1") (pintype "passive"))
      (node (ref "R72") (pin "1") (pinfunction "1_1") (pintype "passive"))
      (node (ref "R73") (pin "1") (pinfunction "1_1") (pintype "passive"))
      (node (ref "R74") (pin "1") (pinfunction "1_1") (pintype "passive"))
      (node (ref "R75") (pin "1") (pinfunction "1_1") (pintype "passive"))
      (node (ref "R76") (pin "1") (pinfunction "1_1") (pintype "passive"))
      (node (ref "R77") (pin "1") (pinfunction "1_1") (pintype "passive"))
      (node (ref "R78") (pin "1") (pinfunction "1_1") (pintype "passive"))
      (node (ref "R79") (pin "1") (pinfunction "1_1") (pintype "passive"))
      (node (ref "R8") (pin "1") (pinfunction "1_1") (pintype "passive"))
      (node (ref "R80") (pin "1") (pinfunction "1_1") (pintype "passive"))
      (node (ref "R81") (pin "1") (pinfunction "1_1") (pintype "passive"))
      (node (ref "R82") (pin "1") (pinfunction "1_1") (pintype "passive"))
      (node (ref "R83") (pin "1") (pinfunction "1_1") (pintype "passive"))
      (node (ref "R84") (pin "1") (pinfunction "1_1") (pintype "passive"))
      (node (ref "R85") (pin "1") (pinfunction "1_1") (pintype "passive"))
      (node (ref "R86") (pin "1") (pinfunction "1_1") (pintype "passive"))
      (node (ref "R87") (pin "1") (pinfunction "1_1") (pintype "passive"))
      (node (ref "R88") (pin "1") (pinfunction "1_1") (pintype "passive"))
      (node (ref "R89") (pin "1") (pinfunction "1_1") (pintype "passive"))
      (node (ref "R9") (pin "1") (pinfunction "1_1") (pintype "passive"))
    )
    (net (code "2") (name "AC0") (class "Default")
      (node (ref "D40TOP") (pin "4") (pinfunction "1_4") (pintype "passive"))
      (node (ref "E40") (pin "7") (pinfunction "7_7") (pintype "passive"))
      (node (ref "T43") (pin "2") (pinfunction "B_2") (pintype "passive"))
    )
    (net (code "3") (name "AC1") (class "Default")
      (node (ref "D40BOT") (pin "2") (pinfunction "1_2") (pintype "passive"))
      (node (ref "E40") (pin "4") (pinfunction "4_4") (pintype "passive"))
      (node (ref "T44") (pin "2") (pinfunction "B_2") (pintype "passive"))
    )
    (net (code "4") (name "AC2") (class "Default")
      (node (ref "D40TOP") (pin "12") (pinfunction "1_12") (pintype "passive"))
      (node (ref "E40") (pin "21") (pinfunction "21_21") (pintype "passive"))
      (node (ref "T45") (pin "2") (pinfunction "B_2") (pintype "passive"))
    )
    (net (code "5") (name "AC3") (class "Default")
      (node (ref "D40BOT") (pin "9") (pinfunction "1_9") (pintype "passive"))
      (node (ref "E40") (pin "14") (pinfunction "14_14") (pintype "passive"))
      (node (ref "T46") (pin "2") (pinfunction "B_2") (pintype "passive"))
    )
    (net (code "6") (name "AC4") (class "Default")
      (node (ref "D40TOP") (pin "17") (pinfunction "1_17") (pintype "passive"))
      (node (ref "E40") (pin "31") (pinfunction "31_31") (pintype "passive"))
      (node (ref "T47") (pin "2") (pinfunction "B_2") (pintype "passive"))
    )
    (net (code "7") (name "AC5") (class "Default")
      (node (ref "D40BOT") (pin "16") (pinfunction "1_16") (pintype "passive"))
      (node (ref "E40") (pin "28") (pinfunction "28_28") (pintype "passive"))
      (node (ref "T48") (pin "2") (pinfunction "B_2") (pintype "passive"))
    )
    (net (code "8") (name "AC6") (class "Default")
      (node (ref "E40TOP") (pin "4") (pinfunction "1_4") (pintype "passive"))
      (node (ref "F40") (pin "7") (pinfunction "7_7") (pintype "passive"))
      (node (ref "T49") (pin "2") (pinfunction "B_2") (pintype "passive"))
    )
    (net (code "9") (name "AC7") (class "Default")
      (node (ref "E40BOT") (pin "2") (pinfunction "1_2") (pintype "passive"))
      (node (ref "F40") (pin "4") (pinfunction "4_4") (pintype "passive"))
      (node (ref "T50") (pin "2") (pinfunction "B_2") (pintype "passive"))
    )
    (net (code "10") (name "AC8") (class "Default")
      (node (ref "E40TOP") (pin "12") (pinfunction "1_12") (pintype "passive"))
      (node (ref "F40") (pin "21") (pinfunction "21_21") (pintype "passive"))
      (node (ref "T51") (pin "2") (pinfunction "B_2") (pintype "passive"))
    )
    (net (code "11") (name "AC9") (class "Default")
      (node (ref "E40BOT") (pin "9") (pinfunction "1_9") (pintype "passive"))
      (node (ref "F40") (pin "14") (pinfunction "14_14") (pintype "passive"))
      (node (ref "T52") (pin "2") (pinfunction "B_2") (pintype "passive"))
    )
    (net (code "12") (name "AC10") (class "Default")
      (node (ref "E40TOP") (pin "17") (pinfunction "1_17") (pintype "passive"))
      (node (ref "F40") (pin "31") (pinfunction "31_31") (pintype "passive"))
      (node (ref "T53") (pin "2") (pinfunction "B_2") (pintype "passive"))
    )
    (net (code "13") (name "AC11") (class "Default")
      (node (ref "E40BOT") (pin "16") (pinfunction "1_16") (pintype "passive"))
      (node (ref "F40") (pin "28") (pinfunction "28_28") (pintype "passive"))
      (node (ref "T54") (pin "2") (pinfunction "B_2") (pintype "passive"))
    )
    (net (code "14") (name "AND") (class "Default")
      (node (ref "D40") (pin "2") (pinfunction "2_2") (pintype "passive"))
      (node (ref "F40BOT") (pin "1") (pinfunction "1_1") (pintype "passive"))
      (node (ref "T82") (pin "2") (pinfunction "B_2") (pintype "passive"))
    )
    (net (code "15") (name "BREAK") (class "Default")
      (node (ref "D40") (pin "22") (pinfunction "22_22") (pintype "passive"))
      (node (ref "F40BOT") (pin "12") (pinfunction "1_12") (pintype "passive"))
      (node (ref "T81") (pin "2") (pinfunction "B_2") (pintype "passive"))
    )
    (net (code "16") (name "CA") (class "Default")
      (node (ref "D40") (pin "32") (pinfunction "32_32") (pintype "passive"))
      (node (ref "F40BOT") (pin "18") (pinfunction "1_18") (pintype "passive"))
      (node (ref "T80") (pin "2") (pinfunction "B_2") (pintype "passive"))
    )
    (net (code "17") (name "DCA") (class "Default")
      (node (ref "D40") (pin "8") (pinfunction "8_8") (pintype "passive"))
      (node (ref "F40BOT") (pin "4") (pinfunction "1_4") (pintype "passive"))
      (node (ref "T85") (pin "2") (pinfunction "B_2") (pintype "passive"))
    )
    (net (code "18") (name "DEFER") (class "Default")
      (node (ref "D40") (pin "26") (pinfunction "26_26") (pintype "passive"))
      (node (ref "F40BOT") (pin "15") (pinfunction "1_15") (pintype "passive"))
      (node (ref "T78") (pin "2") (pinfunction "B_2") (pintype "passive"))
    )
    (net (code "19") (name "DF0") (class "Default")
      (node (ref "C40") (pin "1") (pinfunction "1_1") (pintype "passive"))
      (node (ref "C40TOP") (pin "1") (pinfunction "1_1") (pintype "passive"))
      (node (ref "T1") (pin "2") (pinfunction "B_2") (pintype "passive"))
    )
    (net (code "20") (name "DF1") (class "Default")
      (node (ref "C40") (pin "10") (pinfunction "10_10") (pintype "passive"))
      (node (ref "C40BOT") (pin "5") (pinfunction "1_5") (pintype "passive"))
      (node (ref "T2") (pin "2") (pinfunction "B_2") (pintype "passive"))
    )
    (net (code "21") (name "DF2") (class "Default")
      (node (ref "C40") (pin "11") (pinfunction "11_11") (pintype "passive"))
      (node (ref "C40TOP") (pin "6") (pinfunction "1_6") (pintype "passive"))
      (node (ref "T3") (pin "2") (pinfunction "B_2") (pintype "passive"))
    )
    (net (code "22") (name "EXECUTE") (class "Default")
      (node (ref "D40") (pin "28") (pinfunction "28_28") (pintype "passive"))
      (node (ref "F40BOT") (pin "16") (pinfunction "1_16") (pintype "passive"))
      (node (ref "T77") (pin "2") (pinfunction "B_2") (pintype "passive"))
    )
    (net (code "23") (name "FETCH") (class "Default")
      (node (ref "D40") (pin "24") (pinfunction "24_24") (pintype "passive"))
      (node (ref "F40BOT") (pin "14") (pinfunction "1_14") (pintype "passive"))
      (node (ref "T76") (pin "2") (pinfunction "B_2") (pintype "passive"))
    )
    (net (code "24") (name "GND") (class "Default")
      (node (ref "C40") (pin "17") (pinfunction "17_17") (pintype "passive"))
      (node (ref "C40") (pin "18") (pinfunction "18_18") (pintype "passive"))
      (node (ref "C40") (pin "19") (pinfunction "19_19") (pintype "passive"))
      (node (ref "C40") (pin "20") (pinfunction "20_20") (pintype "passive"))
      (node (ref "C40BOT") (pin "13") (pinfunction "1_13") (pintype "passive"))
      (node (ref "D40") (pin "17") (pinfunction "17_17") (pintype "passive"))
      (node (ref "D40") (pin "18") (pinfunction "18_18") (pintype "passive"))
      (node (ref "D40") (pin "19") (pinfunction "19_19") (pintype "passive"))
      (node (ref "D40") (pin "20") (pinfunction "20_20") (pintype "passive"))
      (node (ref "D40BOT") (pin "13") (pinfunction "1_13") (pintype "passive"))
      (node (ref "E40") (pin "17") (pinfunction "17_17") (pintype "passive"))
      (node (ref "E40") (pin "18") (pinfunction "18_18") (pintype "passive"))
      (node (ref "E40") (pin "19") (pinfunction "19_19") (pintype "passive"))
      (node (ref "E40") (pin "20") (pinfunction "20_20") (pintype "passive"))
      (node (ref "E40BOT") (pin "13") (pinfunction "1_13") (pintype "passive"))
      (node (ref "F40") (pin "17") (pinfunction "17_17") (pintype "passive"))
      (node (ref "F40") (pin "18") (pinfunction "18_18") (pintype "passive"))
      (node (ref "F40") (pin "19") (pinfunction "19_19") (pintype "passive"))
      (node (ref "F40") (pin "20") (pinfunction "20_20") (pintype "passive"))
      (node (ref "F40BOT") (pin "13") (pinfunction "1_13") (pintype "passive"))
      (node (ref "GND1") (pin "1") (pinfunction "1_1") (pintype "passive"))
      (node (ref "GND2") (pin "1") (pinfunction "1_1") (pintype "passive"))
      (node (ref "T1") (pin "1") (pinfunction "E_1") (pintype "passive"))
      (node (ref "T10") (pin "1") (pinfunction "E_1") (pintype "passive"))
      (node (ref "T11") (pin "1") (pinfunction "E_1") (pintype "passive"))
      (node (ref "T12") (pin "1") (pinfunction "E_1") (pintype "passive"))
      (node (ref "T13") (pin "1") (pinfunction "E_1") (pintype "passive"))
      (node (ref "T14") (pin "1") (pinfunction "E_1") (pintype "passive"))
      (node (ref "T15") (pin "1") (pinfunction "E_1") (pintype "passive"))
      (node (ref "T16") (pin "1") (pinfunction "E_1") (pintype "passive"))
      (node (ref "T17") (pin "1") (pinfunction "E_1") (pintype "passive"))
      (node (ref "T18") (pin "1") (pinfunction "E_1") (pintype "passive"))
      (node (ref "T19") (pin "1") (pinfunction "E_1") (pintype "passive"))
      (node (ref "T2") (pin "1") (pinfunction "E_1") (pintype "passive"))
      (node (ref "T20") (pin "1") (pinfunction "E_1") (pintype "passive"))
      (node (ref "T21") (pin "1") (pinfunction "E_1") (pintype "passive"))
      (node (ref "T22") (pin "1") (pinfunction "E_1") (pintype "passive"))
      (node (ref "T23") (pin "1") (pinfunction "E_1") (pintype "passive"))
      (node (ref "T24") (pin "1") (pinfunction "E_1") (pintype "passive"))
      (node (ref "T25") (pin "1") (pinfunction "E_1") (pintype "passive"))
      (node (ref "T26") (pin "1") (pinfunction "E_1") (pintype "passive"))
      (node (ref "T27") (pin "1") (pinfunction "E_1") (pintype "passive"))
      (node (ref "T28") (pin "1") (pinfunction "E_1") (pintype "passive"))
      (node (ref "T29") (pin "1") (pinfunction "E_1") (pintype "passive"))
      (node (ref "T3") (pin "1") (pinfunction "E_1") (pintype "passive"))
      (node (ref "T30") (pin "1") (pinfunction "E_1") (pintype "passive"))
      (node (ref "T31") (pin "1") (pinfunction "E_1") (pintype "passive"))
      (node (ref "T32") (pin "1") (pinfunction "E_1") (pintype "passive"))
      (node (ref "T33") (pin "1") (pinfunction "E_1") (pintype "passive"))
      (node (ref "T34") (pin "1") (pinfunction "E_1") (pintype "passive"))
      (node (ref "T35") (pin "1") (pinfunction "E_1") (pintype "passive"))
      (node (ref "T36") (pin "1") (pinfunction "E_1") (pintype "passive"))
      (node (ref "T37") (pin "1") (pinfunction "E_1") (pintype "passive"))
      (node (ref "T38") (pin "1") (pinfunction "E_1") (pintype "passive"))
      (node (ref "T39") (pin "1") (pinfunction "E_1") (pintype "passive"))
      (node (ref "T4") (pin "1") (pinfunction "E_1") (pintype "passive"))
      (node (ref "T40") (pin "1") (pinfunction "E_1") (pintype "passive"))
      (node (ref "T41") (pin "1") (pinfunction "E_1") (pintype "passive"))
      (node (ref "T42") (pin "1") (pinfunction "E_1") (pintype "passive"))
      (node (ref "T43") (pin "1") (pinfunction "E_1") (pintype "passive"))
      (node (ref "T44") (pin "1") (pinfunction "E_1") (pintype "passive"))
      (node (ref "T45") (pin "1") (pinfunction "E_1") (pintype "passive"))
      (node (ref "T46") (pin "1") (pinfunction "E_1") (pintype "passive"))
      (node (ref "T47") (pin "1") (pinfunction "E_1") (pintype "passive"))
      (node (ref "T48") (pin "1") (pinfunction "E_1") (pintype "passive"))
      (node (ref "T49") (pin "1") (pinfunction "E_1") (pintype "passive"))
      (node (ref "T5") (pin "1") (pinfunction "E_1") (pintype "passive"))
      (node (ref "T50") (pin "1") (pinfunction "E_1") (pintype "passive"))
      (node (ref "T51") (pin "1") (pinfunction "E_1") (pintype "passive"))
      (node (ref "T52") (pin "1") (pinfunction "E_1") (pintype "passive"))
      (node (ref "T53") (pin "1") (pinfunction "E_1") (pintype "passive"))
      (node (ref "T54") (pin "1") (pinfunction "E_1") (pintype "passive"))
      (node (ref "T55") (pin "1") (pinfunction "E_1") (pintype "passive"))
      (node (ref "T56") (pin "1") (pinfunction "E_1") (pintype "passive"))
      (node (ref "T57") (pin "1") (pinfunction "E_1") (pintype "passive"))
      (node (ref "T58") (pin "1") (pinfunction "E_1") (pintype "passive"))
      (node (ref "T59") (pin "1") (pinfunction "E_1") (pintype "passive"))
      (node (ref "T6") (pin "1") (pinfunction "E_1") (pintype "passive"))
      (node (ref "T60") (pin "1") (pinfunction "E_1") (pintype "passive"))
      (node (ref "T61") (pin "1") (pinfunction "E_1") (pintype "passive"))
      (node (ref "T62") (pin "1") (pinfunction "E_1") (pintype "passive"))
      (node (ref "T63") (pin "1") (pinfunction "E_1") (pintype "passive"))
      (node (ref "T64") (pin "1") (pinfunction "E_1") (pintype "passive"))
      (node (ref "T65") (pin "1") (pinfunction "E_1") (pintype "passive"))
      (node (ref "T66") (pin "1") (pinfunction "E_1") (pintype "passive"))
      (node (ref "T67") (pin "1") (pinfunction "E_1") (pintype "passive"))
      (node (ref "T68") (pin "1") (pinfunction "E_1") (pintype "passive"))
      (node (ref "T69") (pin "1") (pinfunction "E_1") (pintype "passive"))
      (node (ref "T7") (pin "1") (pinfunction "E_1") (pintype "passive"))
      (node (ref "T70") (pin "1") (pinfunction "E_1") (pintype "passive"))
      (node (ref "T71") (pin "1") (pinfunction "E_1") (pintype "passive"))
      (node (ref "T72") (pin "1") (pinfunction "E_1") (pintype "passive"))
      (node (ref "T73") (pin "1") (pinfunction "E_1") (pintype "passive"))
      (node (ref "T74") (pin "1") (pinfunction "E_1") (pintype "passive"))
      (node (ref "T75") (pin "1") (pinfunction "E_1") (pintype "passive"))
      (node (ref "T76") (pin "1") (pinfunction "E_1") (pintype "passive"))
      (node (ref "T77") (pin "1") (pinfunction "E_1") (pintype "passive"))
      (node (ref "T78") (pin "1") (pinfunction "E_1") (pintype "passive"))
      (node (ref "T79") (pin "1") (pinfunction "E_1") (pintype "passive"))
      (node (ref "T8") (pin "1") (pinfunction "E_1") (pintype "passive"))
      (node (ref "T80") (pin "1") (pinfunction "E_1") (pintype "passive"))
      (node (ref "T81") (pin "1") (pinfunction "E_1") (pintype "passive"))
      (node (ref "T82") (pin "1") (pinfunction "E_1") (pintype "passive"))
      (node (ref "T83") (pin "1") (pinfunction "E_1") (pintype "passive"))
      (node (ref "T84") (pin "1") (pinfunction "E_1") (pintype "passive"))
      (node (ref "T85") (pin "1") (pinfunction "E_1") (pintype "passive"))
      (node (ref "T86") (pin "1") (pinfunction "E_1") (pintype "passive"))
      (node (ref "T87") (pin "1") (pinfunction "E_1") (pintype "passive"))
      (node (ref "T88") (pin "1") (pinfunction "E_1") (pintype "passive"))
      (node (ref "T89") (pin "1") (pinfunction "E_1") (pintype "passive"))
      (node (ref "T9") (pin "1") (pinfunction "E_1") (pintype "passive"))
    )
    (net (code "25") (name "IF0") (class "Default")
      (node (ref "C40") (pin "24") (pinfunction "24_24") (pintype "passive"))
      (node (ref "C40BOT") (pin "14") (pinfunction "1_14") (pintype "passive"))
      (node (ref "T4") (pin "2") (pinfunction "B_2") (pintype "passive"))
    )
    (net (code "26") (name "IF1") (class "Default")
      (node (ref "C40") (pin "25") (pinfunction "25_25") (pintype "passive"))
      (node (ref "C40TOP") (pin "14") (pinfunction "1_14") (pintype "passive"))
      (node (ref "T5") (pin "2") (pinfunction "B_2") (pintype "passive"))
    )
    (net (code "27") (name "IF2") (class "Default")
      (node (ref "C40") (pin "34") (pinfunction "34_34") (pintype "passive"))
      (node (ref "C40BOT") (pin "19") (pinfunction "1_19") (pintype "passive"))
      (node (ref "T6") (pin "2") (pinfunction "B_2") (pintype "passive"))
    )
    (net (code "28") (name "ION") (class "Default")
      (node (ref "D40") (pin "34") (pinfunction "34_34") (pintype "passive"))
      (node (ref "F40BOT") (pin "19") (pinfunction "1_19") (pintype "passive"))
      (node (ref "T73") (pin "2") (pinfunction "B_2") (pintype "passive"))
    )
    (net (code "29") (name "IOT") (class "Default")
      (node (ref "D40") (pin "23") (pinfunction "23_23") (pintype "passive"))
      (node (ref "F40TOP") (pin "13") (pinfunction "1_13") (pintype "passive"))
      (node (ref "T88") (pin "2") (pinfunction "B_2") (pintype "passive"))
    )
    (net (code "30") (name "ISZ") (class "Default")
      (node (ref "D40") (pin "6") (pinfunction "6_6") (pintype "passive"))
      (node (ref "F40BOT") (pin "3") (pinfunction "1_3") (pintype "passive"))
      (node (ref "T84") (pin "2") (pinfunction "B_2") (pintype "passive"))
    )
    (net (code "31") (name "JMP") (class "Default")
      (node (ref "D40") (pin "12") (pinfunction "12_12") (pintype "passive"))
      (node (ref "F40BOT") (pin "6") (pinfunction "1_6") (pintype "passive"))
      (node (ref "T87") (pin "2") (pinfunction "B_2") (pintype "passive"))
    )
    (net (code "32") (name "JMS") (class "Default")
      (node (ref "D40") (pin "10") (pinfunction "10_10") (pintype "passive"))
      (node (ref "F40BOT") (pin "5") (pinfunction "1_5") (pintype "passive"))
      (node (ref "T86") (pin "2") (pinfunction "B_2") (pintype "passive"))
    )
    (net (code "33") (name "LINK") (class "Default")
      (node (ref "C40") (pin "28") (pinfunction "28_28") (pintype "passive"))
      (node (ref "C40BOT") (pin "16") (pinfunction "1_16") (pintype "passive"))
      (node (ref "T72") (pin "2") (pinfunction "B_2") (pintype "passive"))
    )
    (net (code "34") (name "MA0") (class "Default")
      (node (ref "D40TOP") (pin "2") (pinfunction "1_2") (pintype "passive"))
      (node (ref "E40") (pin "3") (pinfunction "3_3") (pintype "passive"))
      (node (ref "T19") (pin "2") (pinfunction "B_2") (pintype "passive"))
    )
    (net (code "35") (name "MA1") (class "Default")
      (node (ref "D40BOT") (pin "4") (pinfunction "1_4") (pintype "passive"))
      (node (ref "E40") (pin "8") (pinfunction "8_8") (pintype "passive"))
      (node (ref "T20") (pin "2") (pinfunction "B_2") (pintype "passive"))
    )
    (net (code "36") (name "MA2") (class "Default")
      (node (ref "D40TOP") (pin "7") (pinfunction "1_7") (pintype "passive"))
      (node (ref "E40") (pin "13") (pinfunction "13_13") (pintype "passive"))
      (node (ref "T21") (pin "2") (pinfunction "B_2") (pintype "passive"))
    )
    (net (code "37") (name "MA3") (class "Default")
      (node (ref "D40BOT") (pin "12") (pinfunction "1_12") (pintype "passive"))
      (node (ref "E40") (pin "22") (pinfunction "22_22") (pintype "passive"))
      (node (ref "T22") (pin "2") (pinfunction "B_2") (pintype "passive"))
    )
    (net (code "38") (name "MA4") (class "Default")
      (node (ref "D40TOP") (pin "15") (pinfunction "1_15") (pintype "passive"))
      (node (ref "E40") (pin "27") (pinfunction "27_27") (pintype "passive"))
      (node (ref "T23") (pin "2") (pinfunction "B_2") (pintype "passive"))
    )
    (net (code "39") (name "MA5") (class "Default")
      (node (ref "D40BOT") (pin "18") (pinfunction "1_18") (pintype "passive"))
      (node (ref "E40") (pin "32") (pinfunction "32_32") (pintype "passive"))
      (node (ref "T24") (pin "2") (pinfunction "B_2") (pintype "passive"))
    )
    (net (code "40") (name "MA6") (class "Default")
      (node (ref "E40TOP") (pin "2") (pinfunction "1_2") (pintype "passive"))
      (node (ref "F40") (pin "3") (pinfunction "3_3") (pintype "passive"))
      (node (ref "T25") (pin "2") (pinfunction "B_2") (pintype "passive"))
    )
    (net (code "41") (name "MA7") (class "Default")
      (node (ref "E40BOT") (pin "4") (pinfunction "1_4") (pintype "passive"))
      (node (ref "F40") (pin "8") (pinfunction "8_8") (pintype "passive"))
      (node (ref "T26") (pin "2") (pinfunction "B_2") (pintype "passive"))
    )
    (net (code "42") (name "MA8") (class "Default")
      (node (ref "E40TOP") (pin "7") (pinfunction "1_7") (pintype "passive"))
      (node (ref "F40") (pin "13") (pinfunction "13_13") (pintype "passive"))
      (node (ref "T27") (pin "2") (pinfunction "B_2") (pintype "passive"))
    )
    (net (code "43") (name "MA9") (class "Default")
      (node (ref "E40BOT") (pin "12") (pinfunction "1_12") (pintype "passive"))
      (node (ref "F40") (pin "22") (pinfunction "22_22") (pintype "passive"))
      (node (ref "T28") (pin "2") (pinfunction "B_2") (pintype "passive"))
    )
    (net (code "44") (name "MA10") (class "Default")
      (node (ref "E40TOP") (pin "15") (pinfunction "1_15") (pintype "passive"))
      (node (ref "F40") (pin "27") (pinfunction "27_27") (pintype "passive"))
      (node (ref "T29") (pin "2") (pinfunction "B_2") (pintype "passive"))
    )
    (net (code "45") (name "MA11") (class "Default")
      (node (ref "E40BOT") (pin "18") (pinfunction "1_18") (pintype "passive"))
      (node (ref "F40") (pin "32") (pinfunction "32_32") (pintype "passive"))
      (node (ref "T30") (pin "2") (pinfunction "B_2") (pintype "passive"))
    )
    (net (code "46") (name "MB0") (class "Default")
      (node (ref "D40TOP") (pin "3") (pinfunction "1_3") (pintype "passive"))
      (node (ref "E40") (pin "5") (pinfunction "5_5") (pintype "passive"))
      (node (ref "T31") (pin "2") (pinfunction "B_2") (pintype "passive"))
    )
    (net (code "47") (name "MB1") (class "Default")
      (node (ref "D40BOT") (pin "3") (pinfunction "1_3") (pintype "passive"))
      (node (ref "E40") (pin "6") (pinfunction "6_6") (pintype "passive"))
      (node (ref "T32") (pin "2") (pinfunction "B_2") (pintype "passive"))
    )
    (net (code "48") (name "MB2") (class "Default")
      (node (ref "D40TOP") (pin "8") (pinfunction "1_8") (pintype "passive"))
      (node (ref "E40") (pin "15") (pinfunction "15_15") (pintype "passive"))
      (node (ref "T33") (pin "2") (pinfunction "B_2") (pintype "passive"))
    )
    (net (code "49") (name "MB3") (class "Default")
      (node (ref "D40BOT") (pin "11") (pinfunction "1_11") (pintype "passive"))
      (node (ref "E40") (pin "16") (pinfunction "16_16") (pintype "passive"))
      (node (ref "T34") (pin "2") (pinfunction "B_2") (pintype "passive"))
    )
    (net (code "50") (name "MB4") (class "Default")
      (node (ref "D40TOP") (pin "16") (pinfunction "1_16") (pintype "passive"))
      (node (ref "E40") (pin "29") (pinfunction "29_29") (pintype "passive"))
      (node (ref "T35") (pin "2") (pinfunction "B_2") (pintype "passive"))
    )
    (net (code "51") (name "MB5") (class "Default")
      (node (ref "D40BOT") (pin "17") (pinfunction "1_17") (pintype "passive"))
      (node (ref "E40") (pin "30") (pinfunction "30_30") (pintype "passive"))
      (node (ref "T36") (pin "2") (pinfunction "B_2") (pintype "passive"))
    )
    (net (code "52") (name "MB6") (class "Default")
      (node (ref "E40TOP") (pin "3") (pinfunction "1_3") (pintype "passive"))
      (node (ref "F40") (pin "5") (pinfunction "5_5") (pintype "passive"))
      (node (ref "T37") (pin "2") (pinfunction "B_2") (pintype "passive"))
    )
    (net (code "53") (name "MB7") (class "Default")
      (node (ref "E40BOT") (pin "3") (pinfunction "1_3") (pintype "passive"))
      (node (ref "F40") (pin "6") (pinfunction "6_6") (pintype "passive"))
      (node (ref "T38") (pin "2") (pinfunction "B_2") (pintype "passive"))
    )
    (net (code "54") (name "MB8") (class "Default")
      (node (ref "E40TOP") (pin "8") (pinfunction "1_8") (pintype "passive"))
      (node (ref "F40") (pin "15") (pinfunction "15_15") (pintype "passive"))
      (node (ref "T39") (pin "2") (pinfunction "B_2") (pintype "passive"))
    )
    (net (code "55") (name "MB9") (class "Default")
      (node (ref "E40BOT") (pin "11") (pinfunction "1_11") (pintype "passive"))
      (node (ref "F40") (pin "16") (pinfunction "16_16") (pintype "passive"))
      (node (ref "T40") (pin "2") (pinfunction "B_2") (pintype "passive"))
    )
    (net (code "56") (name "MB10") (class "Default")
      (node (ref "E40TOP") (pin "16") (pinfunction "1_16") (pintype "passive"))
      (node (ref "F40") (pin "29") (pinfunction "29_29") (pintype "passive"))
      (node (ref "T41") (pin "2") (pinfunction "B_2") (pintype "passive"))
    )
    (net (code "57") (name "MB11") (class "Default")
      (node (ref "E40BOT") (pin "17") (pinfunction "1_17") (pintype "passive"))
      (node (ref "F40") (pin "30") (pinfunction "30_30") (pintype "passive"))
      (node (ref "T42") (pin "2") (pinfunction "B_2") (pintype "passive"))
    )
    (net (code "58") (name "MQ0") (class "Default")
      (node (ref "D40TOP") (pin "5") (pinfunction "1_5") (pintype "passive"))
      (node (ref "E40") (pin "9") (pinfunction "9_9") (pintype "passive"))
      (node (ref "T55") (pin "2") (pinfunction "B_2") (pintype "passive"))
    )
    (net (code "59") (name "MQ1") (class "Default")
      (node (ref "D40BOT") (pin "1") (pinfunction "1_1") (pintype "passive"))
      (node (ref "E40") (pin "2") (pinfunction "2_2") (pintype "passive"))
      (node (ref "T56") (pin "2") (pinfunction "B_2") (pintype "passive"))
    )
    (net (code "60") (name "MQ2") (class "Default")
      (node (ref "D40TOP") (pin "13") (pinfunction "1_13") (pintype "passive"))
      (node (ref "E40") (pin "23") (pinfunction "23_23") (pintype "passive"))
      (node (ref "T57") (pin "2") (pinfunction "B_2") (pintype "passive"))
    )
    (net (code "61") (name "MQ3") (class "Default")
      (node (ref "D40BOT") (pin "6") (pinfunction "1_6") (pintype "passive"))
      (node (ref "E40") (pin "12") (pinfunction "12_12") (pintype "passive"))
      (node (ref "T58") (pin "2") (pinfunction "B_2") (pintype "passive"))
    )
    (net (code "62") (name "MQ4") (class "Default")
      (node (ref "D40TOP") (pin "18") (pinfunction "1_18") (pintype "passive"))
      (node (ref "E40") (pin "33") (pinfunction "33_33") (pintype "passive"))
      (node (ref "T59") (pin "2") (pinfunction "B_2") (pintype "passive"))
    )
    (net (code "63") (name "MQ5") (class "Default")
      (node (ref "D40BOT") (pin "15") (pinfunction "1_15") (pintype "passive"))
      (node (ref "E40") (pin "26") (pinfunction "26_26") (pintype "passive"))
      (node (ref "T60") (pin "2") (pinfunction "B_2") (pintype "passive"))
    )
    (net (code "64") (name "MQ6") (class "Default")
      (node (ref "E40TOP") (pin "5") (pinfunction "1_5") (pintype "passive"))
      (node (ref "F40") (pin "9") (pinfunction "9_9") (pintype "passive"))
      (node (ref "T61") (pin "2") (pinfunction "B_2") (pintype "passive"))
    )
    (net (code "65") (name "MQ7") (class "Default")
      (node (ref "E40BOT") (pin "1") (pinfunction "1_1") (pintype "passive"))
      (node (ref "F40") (pin "2") (pinfunction "2_2") (pintype "passive"))
      (node (ref "T62") (pin "2") (pinfunction "B_2") (pintype "passive"))
    )
    (net (code "66") (name "MQ8") (class "Default")
      (node (ref "E40TOP") (pin "13") (pinfunction "1_13") (pintype "passive"))
      (node (ref "F40") (pin "23") (pinfunction "23_23") (pintype "passive"))
      (node (ref "T63") (pin "2") (pinfunction "B_2") (pintype "passive"))
    )
    (net (code "67") (name "MQ9") (class "Default")
      (node (ref "E40BOT") (pin "6") (pinfunction "1_6") (pintype "passive"))
      (node (ref "F40") (pin "12") (pinfunction "12_12") (pintype "passive"))
      (node (ref "T64") (pin "2") (pinfunction "B_2") (pintype "passive"))
    )
    (net (code "68") (name "MQ10") (class "Default")
      (node (ref "E40TOP") (pin "18") (pinfunction "1_18") (pintype "passive"))
      (node (ref "F40") (pin "33") (pinfunction "33_33") (pintype "passive"))
      (node (ref "T65") (pin "2") (pinfunction "B_2") (pintype "passive"))
    )
    (net (code "69") (name "MQ11") (class "Default")
      (node (ref "E40BOT") (pin "15") (pinfunction "1_15") (pintype "passive"))
      (node (ref "F40") (pin "26") (pinfunction "26_26") (pintype "passive"))
      (node (ref "T66") (pin "2") (pinfunction "B_2") (pintype "passive"))
    )
    (net (code "70") (name "Net-(AC0-PadA)") (class "Default")
      (node (ref "AC0") (pin "A") (pinfunction "A_A") (pintype "passive"))
      (node (ref "R43") (pin "2") (pinfunction "2_2") (pintype "passive"))
    )
    (net (code "71") (name "Net-(AC1-PadA)") (class "Default")
      (node (ref "AC1") (pin "A") (pinfunction "A_A") (pintype "passive"))
      (node (ref "R44") (pin "2") (pinfunction "2_2") (pintype "passive"))
    )
    (net (code "72") (name "Net-(AC2-PadA)") (class "Default")
      (node (ref "AC2") (pin "A") (pinfunction "A_A") (pintype "passive"))
      (node (ref "R45") (pin "2") (pinfunction "2_2") (pintype "passive"))
    )
    (net (code "73") (name "Net-(AC3-PadA)") (class "Default")
      (node (ref "AC3") (pin "A") (pinfunction "A_A") (pintype "passive"))
      (node (ref "R46") (pin "2") (pinfunction "2_2") (pintype "passive"))
    )
    (net (code "74") (name "Net-(AC4-PadA)") (class "Default")
      (node (ref "AC4") (pin "A") (pinfunction "A_A") (pintype "passive"))
      (node (ref "R47") (pin "2") (pinfunction "2_2") (pintype "passive"))
    )
    (net (code "75") (name "Net-(AC5-PadA)") (class "Default")
      (node (ref "AC5") (pin "A") (pinfunction "A_A") (pintype "passive"))
      (node (ref "R48") (pin "2") (pinfunction "2_2") (pintype "passive"))
    )
    (net (code "76") (name "Net-(AC6-PadA)") (class "Default")
      (node (ref "AC6") (pin "A") (pinfunction "A_A") (pintype "passive"))
      (node (ref "R49") (pin "2") (pinfunction "2_2") (pintype "passive"))
    )
    (net (code "77") (name "Net-(AC7-PadA)") (class "Default")
      (node (ref "AC7") (pin "A") (pinfunction "A_A") (pintype "passive"))
      (node (ref "R50") (pin "2") (pinfunction "2_2") (pintype "passive"))
    )
    (net (code "78") (name "Net-(AC8-PadA)") (class "Default")
      (node (ref "AC8") (pin "A") (pinfunction "A_A") (pintype "passive"))
      (node (ref "R51") (pin "2") (pinfunction "2_2") (pintype "passive"))
    )
    (net (code "79") (name "Net-(AC9-PadA)") (class "Default")
      (node (ref "AC9") (pin "A") (pinfunction "A_A") (pintype "passive"))
      (node (ref "R52") (pin "2") (pinfunction "2_2") (pintype "passive"))
    )
    (net (code "80") (name "Net-(AC10-PadA)") (class "Default")
      (node (ref "AC10") (pin "A") (pinfunction "A_A") (pintype "passive"))
      (node (ref "R53") (pin "2") (pinfunction "2_2") (pintype "passive"))
    )
    (net (code "81") (name "Net-(AC11-PadA)") (class "Default")
      (node (ref "AC11") (pin "A") (pinfunction "A_A") (pintype "passive"))
      (node (ref "R54") (pin "2") (pinfunction "2_2") (pintype "passive"))
    )
    (net (code "82") (name "Net-(AND-PadA)") (class "Default")
      (node (ref "AND") (pin "A") (pinfunction "A_A") (pintype "passive"))
      (node (ref "R82") (pin "2") (pinfunction "2_2") (pintype "passive"))
    )
    (net (code "83") (name "Net-(BREAK-PadA)") (class "Default")
      (node (ref "BREAK") (pin "A") (pinfunction "A_A") (pintype "passive"))
      (node (ref "R81") (pin "2") (pinfunction "2_2") (pintype "passive"))
    )
    (net (code "84") (name "Net-(CURRENTADDRESS-PadA)") (class "Default")
      (node (ref "CURRENTADDRESS") (pin "A") (pinfunction "A_A") (pintype "passive"))
      (node (ref "R80") (pin "2") (pinfunction "2_2") (pintype "passive"))
    )
    (net (code "85") (name "Net-(DCA-PadA)") (class "Default")
      (node (ref "DCA") (pin "A") (pinfunction "A_A") (pintype "passive"))
      (node (ref "R85") (pin "2") (pinfunction "2_2") (pintype "passive"))
    )
    (net (code "86") (name "Net-(DEFER-PadA)") (class "Default")
      (node (ref "DEFER") (pin "A") (pinfunction "A_A") (pintype "passive"))
      (node (ref "R78") (pin "2") (pinfunction "2_2") (pintype "passive"))
    )
    (net (code "87") (name "Net-(DF0-PadA)") (class "Default")
      (node (ref "DF0") (pin "A") (pinfunction "A_A") (pintype "passive"))
      (node (ref "R1") (pin "2") (pinfunction "2_2") (pintype "passive"))
    )
    (net (code "88") (name "Net-(DF1-PadA)") (class "Default")
      (node (ref "DF1") (pin "A") (pinfunction "A_A") (pintype "passive"))
      (node (ref "R2") (pin "2") (pinfunction "2_2") (pintype "passive"))
    )
    (net (code "89") (name "Net-(DF2-PadA)") (class "Default")
      (node (ref "DF2") (pin "A") (pinfunction "A_A") (pintype "passive"))
      (node (ref "R3") (pin "2") (pinfunction "2_2") (pintype "passive"))
    )
    (net (code "90") (name "Net-(EXECUTE-PadA)") (class "Default")
      (node (ref "EXECUTE") (pin "A") (pinfunction "A_A") (pintype "passive"))
      (node (ref "R77") (pin "2") (pinfunction "2_2") (pintype "passive"))
    )
    (net (code "91") (name "Net-(FETCH-PadA)") (class "Default")
      (node (ref "FETCH") (pin "A") (pinfunction "A_A") (pintype "passive"))
      (node (ref "R76") (pin "2") (pinfunction "2_2") (pintype "passive"))
    )
    (net (code "92") (name "Net-(IF0-PadA)") (class "Default")
      (node (ref "IF0") (pin "A") (pinfunction "A_A") (pintype "passive"))
      (node (ref "R4") (pin "2") (pinfunction "2_2") (pintype "passive"))
    )
    (net (code "93") (name "Net-(IF1-PadA)") (class "Default")
      (node (ref "IF1") (pin "A") (pinfunction "A_A") (pintype "passive"))
      (node (ref "R5") (pin "2") (pinfunction "2_2") (pintype "passive"))
    )
    (net (code "94") (name "Net-(IF2-PadA)") (class "Default")
      (node (ref "IF2") (pin "A") (pinfunction "A_A") (pintype "passive"))
      (node (ref "R6") (pin "2") (pinfunction "2_2") (pintype "passive"))
    )
    (net (code "95") (name "Net-(ION-PadA)") (class "Default")
      (node (ref "ION") (pin "A") (pinfunction "A_A") (pintype "passive"))
      (node (ref "R73") (pin "2") (pinfunction "2_2") (pintype "passive"))
    )
    (net (code "96") (name "Net-(IOT-PadA)") (class "Default")
      (node (ref "IOT") (pin "A") (pinfunction "A_A") (pintype "passive"))
      (node (ref "R88") (pin "2") (pinfunction "2_2") (pintype "passive"))
    )
    (net (code "97") (name "Net-(ISZ-PadA)") (class "Default")
      (node (ref "ISZ") (pin "A") (pinfunction "A_A") (pintype "passive"))
      (node (ref "R84") (pin "2") (pinfunction "2_2") (pintype "passive"))
    )
    (net (code "98") (name "Net-(JMP-PadA)") (class "Default")
      (node (ref "JMP") (pin "A") (pinfunction "A_A") (pintype "passive"))
      (node (ref "R87") (pin "2") (pinfunction "2_2") (pintype "passive"))
    )
    (net (code "99") (name "Net-(JMS-PadA)") (class "Default")
      (node (ref "JMS") (pin "A") (pinfunction "A_A") (pintype "passive"))
      (node (ref "R86") (pin "2") (pinfunction "2_2") (pintype "passive"))
    )
    (net (code "100") (name "Net-(LINK-PadA)") (class "Default")
      (node (ref "LINK") (pin "A") (pinfunction "A_A") (pintype "passive"))
      (node (ref "R72") (pin "2") (pinfunction "2_2") (pintype "passive"))
    )
    (net (code "101") (name "Net-(MA0-PadA)") (class "Default")
      (node (ref "MA0") (pin "A") (pinfunction "A_A") (pintype "passive"))
      (node (ref "R19") (pin "2") (pinfunction "2_2") (pintype "passive"))
    )
    (net (code "102") (name "Net-(MA1-PadA)") (class "Default")
      (node (ref "MA1") (pin "A") (pinfunction "A_A") (pintype "passive"))
      (node (ref "R20") (pin "2") (pinfunction "2_2") (pintype "passive"))
    )
    (net (code "103") (name "Net-(MA2-PadA)") (class "Default")
      (node (ref "MA2") (pin "A") (pinfunction "A_A") (pintype "passive"))
      (node (ref "R21") (pin "2") (pinfunction "2_2") (pintype "passive"))
    )
    (net (code "104") (name "Net-(MA3-PadA)") (class "Default")
      (node (ref "MA3") (pin "A") (pinfunction "A_A") (pintype "passive"))
      (node (ref "R22") (pin "2") (pinfunction "2_2") (pintype "passive"))
    )
    (net (code "105") (name "Net-(MA4-PadA)") (class "Default")
      (node (ref "MA4") (pin "A") (pinfunction "A_A") (pintype "passive"))
      (node (ref "R23") (pin "2") (pinfunction "2_2") (pintype "passive"))
    )
    (net (code "106") (name "Net-(MA5-PadA)") (class "Default")
      (node (ref "MA5") (pin "A") (pinfunction "A_A") (pintype "passive"))
      (node (ref "R24") (pin "2") (pinfunction "2_2") (pintype "passive"))
    )
    (net (code "107") (name "Net-(MA6-PadA)") (class "Default")
      (node (ref "MA6") (pin "A") (pinfunction "A_A") (pintype "passive"))
      (node (ref "R25") (pin "2") (pinfunction "2_2") (pintype "passive"))
    )
    (net (code "108") (name "Net-(MA7-PadA)") (class "Default")
      (node (ref "MA7") (pin "A") (pinfunction "A_A") (pintype "passive"))
      (node (ref "R26") (pin "2") (pinfunction "2_2") (pintype "passive"))
    )
    (net (code "109") (name "Net-(MA8-PadA)") (class "Default")
      (node (ref "MA8") (pin "A") (pinfunction "A_A") (pintype "passive"))
      (node (ref "R27") (pin "2") (pinfunction "2_2") (pintype "passive"))
    )
    (net (code "110") (name "Net-(MA9-PadA)") (class "Default")
      (node (ref "MA9") (pin "A") (pinfunction "A_A") (pintype "passive"))
      (node (ref "R28") (pin "2") (pinfunction "2_2") (pintype "passive"))
    )
    (net (code "111") (name "Net-(MA10-PadA)") (class "Default")
      (node (ref "MA10") (pin "A") (pinfunction "A_A") (pintype "passive"))
      (node (ref "R29") (pin "2") (pinfunction "2_2") (pintype "passive"))
    )
    (net (code "112") (name "Net-(MA11-PadA)") (class "Default")
      (node (ref "MA11") (pin "A") (pinfunction "A_A") (pintype "passive"))
      (node (ref "R30") (pin "2") (pinfunction "2_2") (pintype "passive"))
    )
    (net (code "113") (name "Net-(MB0-PadA)") (class "Default")
      (node (ref "MB0") (pin "A") (pinfunction "A_A") (pintype "passive"))
      (node (ref "R31") (pin "2") (pinfunction "2_2") (pintype "passive"))
    )
    (net (code "114") (name "Net-(MB1-PadA)") (class "Default")
      (node (ref "MB1") (pin "A") (pinfunction "A_A") (pintype "passive"))
      (node (ref "R32") (pin "2") (pinfunction "2_2") (pintype "passive"))
    )
    (net (code "115") (name "Net-(MB2-PadA)") (class "Default")
      (node (ref "MB2") (pin "A") (pinfunction "A_A") (pintype "passive"))
      (node (ref "R33") (pin "2") (pinfunction "2_2") (pintype "passive"))
    )
    (net (code "116") (name "Net-(MB3-PadA)") (class "Default")
      (node (ref "MB3") (pin "A") (pinfunction "A_A") (pintype "passive"))
      (node (ref "R34") (pin "2") (pinfunction "2_2") (pintype "passive"))
    )
    (net (code "117") (name "Net-(MB4-PadA)") (class "Default")
      (node (ref "MB4") (pin "A") (pinfunction "A_A") (pintype "passive"))
      (node (ref "R35") (pin "2") (pinfunction "2_2") (pintype "passive"))
    )
    (net (code "118") (name "Net-(MB5-PadA)") (class "Default")
      (node (ref "MB5") (pin "A") (pinfunction "A_A") (pintype "passive"))
      (node (ref "R36") (pin "2") (pinfunction "2_2") (pintype "passive"))
    )
    (net (code "119") (name "Net-(MB6-PadA)") (class "Default")
      (node (ref "MB6") (pin "A") (pinfunction "A_A") (pintype "passive"))
      (node (ref "R37") (pin "2") (pinfunction "2_2") (pintype "passive"))
    )
    (net (code "120") (name "Net-(MB7-PadA)") (class "Default")
      (node (ref "MB7") (pin "A") (pinfunction "A_A") (pintype "passive"))
      (node (ref "R38") (pin "2") (pinfunction "2_2") (pintype "passive"))
    )
    (net (code "121") (name "Net-(MB8-PadA)") (class "Default")
      (node (ref "MB8") (pin "A") (pinfunction "A_A") (pintype "passive"))
      (node (ref "R39") (pin "2") (pinfunction "2_2") (pintype "passive"))
    )
    (net (code "122") (name "Net-(MB9-PadA)") (class "Default")
      (node (ref "MB9") (pin "A") (pinfunction "A_A") (pintype "passive"))
      (node (ref "R40") (pin "2") (pinfunction "2_2") (pintype "passive"))
    )
    (net (code "123") (name "Net-(MB10-PadA)") (class "Default")
      (node (ref "MB10") (pin "A") (pinfunction "A_A") (pintype "passive"))
      (node (ref "R41") (pin "2") (pinfunction "2_2") (pintype "passive"))
    )
    (net (code "124") (name "Net-(MB11-PadA)") (class "Default")
      (node (ref "MB11") (pin "A") (pinfunction "A_A") (pintype "passive"))
      (node (ref "R42") (pin "2") (pinfunction "2_2") (pintype "passive"))
    )
    (net (code "125") (name "Net-(MQ0-PadA)") (class "Default")
      (node (ref "MQ0") (pin "A") (pinfunction "A_A") (pintype "passive"))
      (node (ref "R55") (pin "2") (pinfunction "2_2") (pintype "passive"))
    )
    (net (code "126") (name "Net-(MQ1-PadA)") (class "Default")
      (node (ref "MQ1") (pin "A") (pinfunction "A_A") (pintype "passive"))
      (node (ref "R56") (pin "2") (pinfunction "2_2") (pintype "passive"))
    )
    (net (code "127") (name "Net-(MQ2-PadA)") (class "Default")
      (node (ref "MQ2") (pin "A") (pinfunction "A_A") (pintype "passive"))
      (node (ref "R57") (pin "2") (pinfunction "2_2") (pintype "passive"))
    )
    (net (code "128") (name "Net-(MQ3-PadA)") (class "Default")
      (node (ref "MQ3") (pin "A") (pinfunction "A_A") (pintype "passive"))
      (node (ref "R58") (pin "2") (pinfunction "2_2") (pintype "passive"))
    )
    (net (code "129") (name "Net-(MQ4-PadA)") (class "Default")
      (node (ref "MQ4") (pin "A") (pinfunction "A_A") (pintype "passive"))
      (node (ref "R59") (pin "2") (pinfunction "2_2") (pintype "passive"))
    )
    (net (code "130") (name "Net-(MQ5-PadA)") (class "Default")
      (node (ref "MQ5") (pin "A") (pinfunction "A_A") (pintype "passive"))
      (node (ref "R60") (pin "2") (pinfunction "2_2") (pintype "passive"))
    )
    (net (code "131") (name "Net-(MQ6-PadA)") (class "Default")
      (node (ref "MQ6") (pin "A") (pinfunction "A_A") (pintype "passive"))
      (node (ref "R61") (pin "2") (pinfunction "2_2") (pintype "passive"))
    )
    (net (code "132") (name "Net-(MQ7-PadA)") (class "Default")
      (node (ref "MQ7") (pin "A") (pinfunction "A_A") (pintype "passive"))
      (node (ref "R62") (pin "2") (pinfunction "2_2") (pintype "passive"))
    )
    (net (code "133") (name "Net-(MQ8-PadA)") (class "Default")
      (node (ref "MQ8") (pin "A") (pinfunction "A_A") (pintype "passive"))
      (node (ref "R63") (pin "2") (pinfunction "2_2") (pintype "passive"))
    )
    (net (code "134") (name "Net-(MQ9-PadA)") (class "Default")
      (node (ref "MQ9") (pin "A") (pinfunction "A_A") (pintype "passive"))
      (node (ref "R64") (pin "2") (pinfunction "2_2") (pintype "passive"))
    )
    (net (code "135") (name "Net-(MQ10-PadA)") (class "Default")
      (node (ref "MQ10") (pin "A") (pinfunction "A_A") (pintype "passive"))
      (node (ref "R65") (pin "2") (pinfunction "2_2") (pintype "passive"))
    )
    (net (code "136") (name "Net-(MQ11-PadA)") (class "Default")
      (node (ref "MQ11") (pin "A") (pinfunction "A_A") (pintype "passive"))
      (node (ref "R66") (pin "2") (pinfunction "2_2") (pintype "passive"))
    )
    (net (code "137") (name "Net-(OPR-PadA)") (class "Default")
      (node (ref "OPR") (pin "A") (pinfunction "A_A") (pintype "passive"))
      (node (ref "R89") (pin "2") (pinfunction "2_2") (pintype "passive"))
    )
    (net (code "138") (name "Net-(PAUSE-PadA)") (class "Default")
      (node (ref "PAUSE") (pin "A") (pinfunction "A_A") (pintype "passive"))
      (node (ref "R74") (pin "2") (pinfunction "2_2") (pintype "passive"))
    )
    (net (code "139") (name "Net-(PC0-PadA)") (class "Default")
      (node (ref "PC0") (pin "A") (pinfunction "A_A") (pintype "passive"))
      (node (ref "R7") (pin "2") (pinfunction "2_2") (pintype "passive"))
    )
    (net (code "140") (name "Net-(PC1-PadA)") (class "Default")
      (node (ref "PC1") (pin "A") (pinfunction "A_A") (pintype "passive"))
      (node (ref "R8") (pin "2") (pinfunction "2_2") (pintype "passive"))
    )
    (net (code "141") (name "Net-(PC2-PadA)") (class "Default")
      (node (ref "PC2") (pin "A") (pinfunction "A_A") (pintype "passive"))
      (node (ref "R9") (pin "2") (pinfunction "2_2") (pintype "passive"))
    )
    (net (code "142") (name "Net-(PC3-PadA)") (class "Default")
      (node (ref "PC3") (pin "A") (pinfunction "A_A") (pintype "passive"))
      (node (ref "R10") (pin "2") (pinfunction "2_2") (pintype "passive"))
    )
    (net (code "143") (name "Net-(PC4-PadA)") (class "Default")
      (node (ref "PC4") (pin "A") (pinfunction "A_A") (pintype "passive"))
      (node (ref "R11") (pin "2") (pinfunction "2_2") (pintype "passive"))
    )
    (net (code "144") (name "Net-(PC5-PadA)") (class "Default")
      (node (ref "PC5") (pin "A") (pinfunction "A_A") (pintype "passive"))
      (node (ref "R12") (pin "2") (pinfunction "2_2") (pintype "passive"))
    )
    (net (code "145") (name "Net-(PC6-PadA)") (class "Default")
      (node (ref "PC6") (pin "A") (pinfunction "A_A") (pintype "passive"))
      (node (ref "R13") (pin "2") (pinfunction "2_2") (pintype "passive"))
    )
    (net (code "146") (name "Net-(PC7-PadA)") (class "Default")
      (node (ref "PC7") (pin "A") (pinfunction "A_A") (pintype "passive"))
      (node (ref "R14") (pin "2") (pinfunction "2_2") (pintype "passive"))
    )
    (net (code "147") (name "Net-(PC8-PadA)") (class "Default")
      (node (ref "PC8") (pin "A") (pinfunction "A_A") (pintype "passive"))
      (node (ref "R15") (pin "2") (pinfunction "2_2") (pintype "passive"))
    )
    (net (code "148") (name "Net-(PC9-PadA)") (class "Default")
      (node (ref "PC9") (pin "A") (pinfunction "A_A") (pintype "passive"))
      (node (ref "R16") (pin "2") (pinfunction "2_2") (pintype "passive"))
    )
    (net (code "149") (name "Net-(PC10-PadA)") (class "Default")
      (node (ref "PC10") (pin "A") (pinfunction "A_A") (pintype "passive"))
      (node (ref "R17") (pin "2") (pinfunction "2_2") (pintype "passive"))
    )
    (net (code "150") (name "Net-(PC11-PadA)") (class "Default")
      (node (ref "PC11") (pin "A") (pinfunction "A_A") (pintype "passive"))
      (node (ref "R18") (pin "2") (pinfunction "2_2") (pintype "passive"))
    )
    (net (code "151") (name "Net-(R67-Pad2)") (class "Default")
      (node (ref "R67") (pin "2") (pinfunction "2_2") (pintype "passive"))
      (node (ref "SC0") (pin "A") (pinfunction "A_A") (pintype "passive"))
    )
    (net (code "152") (name "Net-(R68-Pad2)") (class "Default")
      (node (ref "R68") (pin "2") (pinfunction "2_2") (pintype "passive"))
      (node (ref "SC1") (pin "A") (pinfunction "A_A") (pintype "passive"))
    )
    (net (code "153") (name "Net-(R69-Pad2)") (class "Default")
      (node (ref "R69") (pin "2") (pinfunction "2_2") (pintype "passive"))
      (node (ref "SC2") (pin "A") (pinfunction "A_A") (pintype "passive"))
    )
    (net (code "154") (name "Net-(R70-Pad2)") (class "Default")
      (node (ref "R70") (pin "2") (pinfunction "2_2") (pintype "passive"))
      (node (ref "SC3") (pin "A") (pinfunction "A_A") (pintype "passive"))
    )
    (net (code "155") (name "Net-(R71-Pad2)") (class "Default")
      (node (ref "R71") (pin "2") (pinfunction "2_2") (pintype "passive"))
      (node (ref "SC4") (pin "A") (pinfunction "A_A") (pintype "passive"))
    )
    (net (code "156") (name "Net-(R75-Pad2)") (class "Default")
      (node (ref "R75") (pin "2") (pinfunction "2_2") (pintype "passive"))
      (node (ref "RUN") (pin "A") (pinfunction "A_A") (pintype "passive"))
    )
    (net (code "157") (name "Net-(R79-Pad2)") (class "Default")
      (node (ref "R79") (pin "2") (pinfunction "2_2") (pintype "passive"))
      (node (ref "WORDCOUNT") (pin "A") (pinfunction "A_A") (pintype "passive"))
    )
    (net (code "158") (name "Net-(R83-Pad2)") (class "Default")
      (node (ref "R83") (pin "2") (pinfunction "2_2") (pintype "passive"))
      (node (ref "TAD") (pin "A") (pinfunction "A_A") (pintype "passive"))
    )
    (net (code "159") (name "Net-(T1-C)") (class "Default")
      (node (ref "DF0") (pin "B") (pinfunction "B_B") (pintype "passive"))
      (node (ref "T1") (pin "3") (pinfunction "C_3") (pintype "passive"))
    )
    (net (code "160") (name "Net-(T2-C)") (class "Default")
      (node (ref "DF1") (pin "B") (pinfunction "B_B") (pintype "passive"))
      (node (ref "T2") (pin "3") (pinfunction "C_3") (pintype "passive"))
    )
    (net (code "161") (name "Net-(T3-C)") (class "Default")
      (node (ref "DF2") (pin "B") (pinfunction "B_B") (pintype "passive"))
      (node (ref "T3") (pin "3") (pinfunction "C_3") (pintype "passive"))
    )
    (net (code "162") (name "Net-(T4-C)") (class "Default")
      (node (ref "IF0") (pin "B") (pinfunction "B_B") (pintype "passive"))
      (node (ref "T4") (pin "3") (pinfunction "C_3") (pintype "passive"))
    )
    (net (code "163") (name "Net-(T5-C)") (class "Default")
      (node (ref "IF1") (pin "B") (pinfunction "B_B") (pintype "passive"))
      (node (ref "T5") (pin "3") (pinfunction "C_3") (pintype "passive"))
    )
    (net (code "164") (name "Net-(T6-C)") (class "Default")
      (node (ref "IF2") (pin "B") (pinfunction "B_B") (pintype "passive"))
      (node (ref "T6") (pin "3") (pinfunction "C_3") (pintype "passive"))
    )
    (net (code "165") (name "Net-(T7-C)") (class "Default")
      (node (ref "PC0") (pin "B") (pinfunction "B_B") (pintype "passive"))
      (node (ref "T7") (pin "3") (pinfunction "C_3") (pintype "passive"))
    )
    (net (code "166") (name "Net-(T8-C)") (class "Default")
      (node (ref "PC1") (pin "B") (pinfunction "B_B") (pintype "passive"))
      (node (ref "T8") (pin "3") (pinfunction "C_3") (pintype "passive"))
    )
    (net (code "167") (name "Net-(T9-C)") (class "Default")
      (node (ref "PC2") (pin "B") (pinfunction "B_B") (pintype "passive"))
      (node (ref "T9") (pin "3") (pinfunction "C_3") (pintype "passive"))
    )
    (net (code "168") (name "Net-(T10-C)") (class "Default")
      (node (ref "PC3") (pin "B") (pinfunction "B_B") (pintype "passive"))
      (node (ref "T10") (pin "3") (pinfunction "C_3") (pintype "passive"))
    )
    (net (code "169") (name "Net-(T11-C)") (class "Default")
      (node (ref "PC4") (pin "B") (pinfunction "B_B") (pintype "passive"))
      (node (ref "T11") (pin "3") (pinfunction "C_3") (pintype "passive"))
    )
    (net (code "170") (name "Net-(T12-C)") (class "Default")
      (node (ref "PC5") (pin "B") (pinfunction "B_B") (pintype "passive"))
      (node (ref "T12") (pin "3") (pinfunction "C_3") (pintype "passive"))
    )
    (net (code "171") (name "Net-(T13-C)") (class "Default")
      (node (ref "PC6") (pin "B") (pinfunction "B_B") (pintype "passive"))
      (node (ref "T13") (pin "3") (pinfunction "C_3") (pintype "passive"))
    )
    (net (code "172") (name "Net-(T14-C)") (class "Default")
      (node (ref "PC7") (pin "B") (pinfunction "B_B") (pintype "passive"))
      (node (ref "T14") (pin "3") (pinfunction "C_3") (pintype "passive"))
    )
    (net (code "173") (name "Net-(T15-C)") (class "Default")
      (node (ref "PC8") (pin "B") (pinfunction "B_B") (pintype "passive"))
      (node (ref "T15") (pin "3") (pinfunction "C_3") (pintype "passive"))
    )
    (net (code "174") (name "Net-(T16-C)") (class "Default")
      (node (ref "PC9") (pin "B") (pinfunction "B_B") (pintype "passive"))
      (node (ref "T16") (pin "3") (pinfunction "C_3") (pintype "passive"))
    )
    (net (code "175") (name "Net-(T17-C)") (class "Default")
      (node (ref "PC10") (pin "B") (pinfunction "B_B") (pintype "passive"))
      (node (ref "T17") (pin "3") (pinfunction "C_3") (pintype "passive"))
    )
    (net (code "176") (name "Net-(T18-C)") (class "Default")
      (node (ref "PC11") (pin "B") (pinfunction "B_B") (pintype "passive"))
      (node (ref "T18") (pin "3") (pinfunction "C_3") (pintype "passive"))
    )
    (net (code "177") (name "Net-(T19-C)") (class "Default")
      (node (ref "MA0") (pin "B") (pinfunction "B_B") (pintype "passive"))
      (node (ref "T19") (pin "3") (pinfunction "C_3") (pintype "passive"))
    )
    (net (code "178") (name "Net-(T20-C)") (class "Default")
      (node (ref "MA1") (pin "B") (pinfunction "B_B") (pintype "passive"))
      (node (ref "T20") (pin "3") (pinfunction "C_3") (pintype "passive"))
    )
    (net (code "179") (name "Net-(T21-C)") (class "Default")
      (node (ref "MA2") (pin "B") (pinfunction "B_B") (pintype "passive"))
      (node (ref "T21") (pin "3") (pinfunction "C_3") (pintype "passive"))
    )
    (net (code "180") (name "Net-(T22-C)") (class "Default")
      (node (ref "MA3") (pin "B") (pinfunction "B_B") (pintype "passive"))
      (node (ref "T22") (pin "3") (pinfunction "C_3") (pintype "passive"))
    )
    (net (code "181") (name "Net-(T23-C)") (class "Default")
      (node (ref "MA4") (pin "B") (pinfunction "B_B") (pintype "passive"))
      (node (ref "T23") (pin "3") (pinfunction "C_3") (pintype "passive"))
    )
    (net (code "182") (name "Net-(T24-C)") (class "Default")
      (node (ref "MA5") (pin "B") (pinfunction "B_B") (pintype "passive"))
      (node (ref "T24") (pin "3") (pinfunction "C_3") (pintype "passive"))
    )
    (net (code "183") (name "Net-(T25-C)") (class "Default")
      (node (ref "MA6") (pin "B") (pinfunction "B_B") (pintype "passive"))
      (node (ref "T25") (pin "3") (pinfunction "C_3") (pintype "passive"))
    )
    (net (code "184") (name "Net-(T26-C)") (class "Default")
      (node (ref "MA7") (pin "B") (pinfunction "B_B") (pintype "passive"))
      (node (ref "T26") (pin "3") (pinfunction "C_3") (pintype "passive"))
    )
    (net (code "185") (name "Net-(T27-C)") (class "Default")
      (node (ref "MA8") (pin "B") (pinfunction "B_B") (pintype "passive"))
      (node (ref "T27") (pin "3") (pinfunction "C_3") (pintype "passive"))
    )
    (net (code "186") (name "Net-(T28-C)") (class "Default")
      (node (ref "MA9") (pin "B") (pinfunction "B_B") (pintype "passive"))
      (node (ref "T28") (pin "3") (pinfunction "C_3") (pintype "passive"))
    )
    (net (code "187") (name "Net-(T29-C)") (class "Default")
      (node (ref "MA10") (pin "B") (pinfunction "B_B") (pintype "passive"))
      (node (ref "T29") (pin "3") (pinfunction "C_3") (pintype "passive"))
    )
    (net (code "188") (name "Net-(T30-C)") (class "Default")
      (node (ref "MA11") (pin "B") (pinfunction "B_B") (pintype "passive"))
      (node (ref "T30") (pin "3") (pinfunction "C_3") (pintype "passive"))
    )
    (net (code "189") (name "Net-(T31-C)") (class "Default")
      (node (ref "MB0") (pin "B") (pinfunction "B_B") (pintype "passive"))
      (node (ref "T31") (pin "3") (pinfunction "C_3") (pintype "passive"))
    )
    (net (code "190") (name "Net-(T32-C)") (class "Default")
      (node (ref "MB1") (pin "B") (pinfunction "B_B") (pintype "passive"))
      (node (ref "T32") (pin "3") (pinfunction "C_3") (pintype "passive"))
    )
    (net (code "191") (name "Net-(T33-C)") (class "Default")
      (node (ref "MB2") (pin "B") (pinfunction "B_B") (pintype "passive"))
      (node (ref "T33") (pin "3") (pinfunction "C_3") (pintype "passive"))
    )
    (net (code "192") (name "Net-(T34-C)") (class "Default")
      (node (ref "MB3") (pin "B") (pinfunction "B_B") (pintype "passive"))
      (node (ref "T34") (pin "3") (pinfunction "C_3") (pintype "passive"))
    )
    (net (code "193") (name "Net-(T35-C)") (class "Default")
      (node (ref "MB4") (pin "B") (pinfunction "B_B") (pintype "passive"))
      (node (ref "T35") (pin "3") (pinfunction "C_3") (pintype "passive"))
    )
    (net (code "194") (name "Net-(T36-C)") (class "Default")
      (node (ref "MB5") (pin "B") (pinfunction "B_B") (pintype "passive"))
      (node (ref "T36") (pin "3") (pinfunction "C_3") (pintype "passive"))
    )
    (net (code "195") (name "Net-(T37-C)") (class "Default")
      (node (ref "MB6") (pin "B") (pinfunction "B_B") (pintype "passive"))
      (node (ref "T37") (pin "3") (pinfunction "C_3") (pintype "passive"))
    )
    (net (code "196") (name "Net-(T38-C)") (class "Default")
      (node (ref "MB7") (pin "B") (pinfunction "B_B") (pintype "passive"))
      (node (ref "T38") (pin "3") (pinfunction "C_3") (pintype "passive"))
    )
    (net (code "197") (name "Net-(T39-C)") (class "Default")
      (node (ref "MB8") (pin "B") (pinfunction "B_B") (pintype "passive"))
      (node (ref "T39") (pin "3") (pinfunction "C_3") (pintype "passive"))
    )
    (net (code "198") (name "Net-(T40-C)") (class "Default")
      (node (ref "MB9") (pin "B") (pinfunction "B_B") (pintype "passive"))
      (node (ref "T40") (pin "3") (pinfunction "C_3") (pintype "passive"))
    )
    (net (code "199") (name "Net-(T41-C)") (class "Default")
      (node (ref "MB10") (pin "B") (pinfunction "B_B") (pintype "passive"))
      (node (ref "T41") (pin "3") (pinfunction "C_3") (pintype "passive"))
    )
    (net (code "200") (name "Net-(T42-C)") (class "Default")
      (node (ref "MB11") (pin "B") (pinfunction "B_B") (pintype "passive"))
      (node (ref "T42") (pin "3") (pinfunction "C_3") (pintype "passive"))
    )
    (net (code "201") (name "Net-(T43-C)") (class "Default")
      (node (ref "AC0") (pin "B") (pinfunction "B_B") (pintype "passive"))
      (node (ref "T43") (pin "3") (pinfunction "C_3") (pintype "passive"))
    )
    (net (code "202") (name "Net-(T44-C)") (class "Default")
      (node (ref "AC1") (pin "B") (pinfunction "B_B") (pintype "passive"))
      (node (ref "T44") (pin "3") (pinfunction "C_3") (pintype "passive"))
    )
    (net (code "203") (name "Net-(T45-C)") (class "Default")
      (node (ref "AC2") (pin "B") (pinfunction "B_B") (pintype "passive"))
      (node (ref "T45") (pin "3") (pinfunction "C_3") (pintype "passive"))
    )
    (net (code "204") (name "Net-(T46-C)") (class "Default")
      (node (ref "AC3") (pin "B") (pinfunction "B_B") (pintype "passive"))
      (node (ref "T46") (pin "3") (pinfunction "C_3") (pintype "passive"))
    )
    (net (code "205") (name "Net-(T47-C)") (class "Default")
      (node (ref "AC4") (pin "B") (pinfunction "B_B") (pintype "passive"))
      (node (ref "T47") (pin "3") (pinfunction "C_3") (pintype "passive"))
    )
    (net (code "206") (name "Net-(T48-C)") (class "Default")
      (node (ref "AC5") (pin "B") (pinfunction "B_B") (pintype "passive"))
      (node (ref "T48") (pin "3") (pinfunction "C_3") (pintype "passive"))
    )
    (net (code "207") (name "Net-(T49-C)") (class "Default")
      (node (ref "AC6") (pin "B") (pinfunction "B_B") (pintype "passive"))
      (node (ref "T49") (pin "3") (pinfunction "C_3") (pintype "passive"))
    )
    (net (code "208") (name "Net-(T50-C)") (class "Default")
      (node (ref "AC7") (pin "B") (pinfunction "B_B") (pintype "passive"))
      (node (ref "T50") (pin "3") (pinfunction "C_3") (pintype "passive"))
    )
    (net (code "209") (name "Net-(T51-C)") (class "Default")
      (node (ref "AC8") (pin "B") (pinfunction "B_B") (pintype "passive"))
      (node (ref "T51") (pin "3") (pinfunction "C_3") (pintype "passive"))
    )
    (net (code "210") (name "Net-(T52-C)") (class "Default")
      (node (ref "AC9") (pin "B") (pinfunction "B_B") (pintype "passive"))
      (node (ref "T52") (pin "3") (pinfunction "C_3") (pintype "passive"))
    )
    (net (code "211") (name "Net-(T53-C)") (class "Default")
      (node (ref "AC10") (pin "B") (pinfunction "B_B") (pintype "passive"))
      (node (ref "T53") (pin "3") (pinfunction "C_3") (pintype "passive"))
    )
    (net (code "212") (name "Net-(T54-C)") (class "Default")
      (node (ref "AC11") (pin "B") (pinfunction "B_B") (pintype "passive"))
      (node (ref "T54") (pin "3") (pinfunction "C_3") (pintype "passive"))
    )
    (net (code "213") (name "Net-(T55-C)") (class "Default")
      (node (ref "MQ0") (pin "B") (pinfunction "B_B") (pintype "passive"))
      (node (ref "T55") (pin "3") (pinfunction "C_3") (pintype "passive"))
    )
    (net (code "214") (name "Net-(T56-C)") (class "Default")
      (node (ref "MQ1") (pin "B") (pinfunction "B_B") (pintype "passive"))
      (node (ref "T56") (pin "3") (pinfunction "C_3") (pintype "passive"))
    )
    (net (code "215") (name "Net-(T57-C)") (class "Default")
      (node (ref "MQ2") (pin "B") (pinfunction "B_B") (pintype "passive"))
      (node (ref "T57") (pin "3") (pinfunction "C_3") (pintype "passive"))
    )
    (net (code "216") (name "Net-(T58-C)") (class "Default")
      (node (ref "MQ3") (pin "B") (pinfunction "B_B") (pintype "passive"))
      (node (ref "T58") (pin "3") (pinfunction "C_3") (pintype "passive"))
    )
    (net (code "217") (name "Net-(T59-C)") (class "Default")
      (node (ref "MQ4") (pin "B") (pinfunction "B_B") (pintype "passive"))
      (node (ref "T59") (pin "3") (pinfunction "C_3") (pintype "passive"))
    )
    (net (code "218") (name "Net-(T60-C)") (class "Default")
      (node (ref "MQ5") (pin "B") (pinfunction "B_B") (pintype "passive"))
      (node (ref "T60") (pin "3") (pinfunction "C_3") (pintype "passive"))
    )
    (net (code "219") (name "Net-(T61-C)") (class "Default")
      (node (ref "MQ6") (pin "B") (pinfunction "B_B") (pintype "passive"))
      (node (ref "T61") (pin "3") (pinfunction "C_3") (pintype "passive"))
    )
    (net (code "220") (name "Net-(T62-C)") (class "Default")
      (node (ref "MQ7") (pin "B") (pinfunction "B_B") (pintype "passive"))
      (node (ref "T62") (pin "3") (pinfunction "C_3") (pintype "passive"))
    )
    (net (code "221") (name "Net-(T63-C)") (class "Default")
      (node (ref "MQ8") (pin "B") (pinfunction "B_B") (pintype "passive"))
      (node (ref "T63") (pin "3") (pinfunction "C_3") (pintype "passive"))
    )
    (net (code "222") (name "Net-(T64-C)") (class "Default")
      (node (ref "MQ9") (pin "B") (pinfunction "B_B") (pintype "passive"))
      (node (ref "T64") (pin "3") (pinfunction "C_3") (pintype "passive"))
    )
    (net (code "223") (name "Net-(T65-C)") (class "Default")
      (node (ref "MQ10") (pin "B") (pinfunction "B_B") (pintype "passive"))
      (node (ref "T65") (pin "3") (pinfunction "C_3") (pintype "passive"))
    )
    (net (code "224") (name "Net-(T66-C)") (class "Default")
      (node (ref "MQ11") (pin "B") (pinfunction "B_B") (pintype "passive"))
      (node (ref "T66") (pin "3") (pinfunction "C_3") (pintype "passive"))
    )
    (net (code "225") (name "Net-(T67-C)") (class "Default")
      (node (ref "SC0") (pin "B") (pinfunction "B_B") (pintype "passive"))
      (node (ref "T67") (pin "3") (pinfunction "C_3") (pintype "passive"))
    )
    (net (code "226") (name "Net-(T68-C)") (class "Default")
      (node (ref "SC1") (pin "B") (pinfunction "B_B") (pintype "passive"))
      (node (ref "T68") (pin "3") (pinfunction "C_3") (pintype "passive"))
    )
    (net (code "227") (name "Net-(T69-C)") (class "Default")
      (node (ref "SC2") (pin "B") (pinfunction "B_B") (pintype "passive"))
      (node (ref "T69") (pin "3") (pinfunction "C_3") (pintype "passive"))
    )
    (net (code "228") (name "Net-(T70-C)") (class "Default")
      (node (ref "SC3") (pin "B") (pinfunction "B_B") (pintype "passive"))
      (node (ref "T70") (pin "3") (pinfunction "C_3") (pintype "passive"))
    )
    (net (code "229") (name "Net-(T71-C)") (class "Default")
      (node (ref "SC4") (pin "B") (pinfunction "B_B") (pintype "passive"))
      (node (ref "T71") (pin "3") (pinfunction "C_3") (pintype "passive"))
    )
    (net (code "230") (name "Net-(T72-C)") (class "Default")
      (node (ref "LINK") (pin "B") (pinfunction "B_B") (pintype "passive"))
      (node (ref "T72") (pin "3") (pinfunction "C_3") (pintype "passive"))
    )
    (net (code "231") (name "Net-(T73-C)") (class "Default")
      (node (ref "ION") (pin "B") (pinfunction "B_B") (pintype "passive"))
      (node (ref "T73") (pin "3") (pinfunction "C_3") (pintype "passive"))
    )
    (net (code "232") (name "Net-(T74-C)") (class "Default")
      (node (ref "PAUSE") (pin "B") (pinfunction "B_B") (pintype "passive"))
      (node (ref "T74") (pin "3") (pinfunction "C_3") (pintype "passive"))
    )
    (net (code "233") (name "Net-(T75-C)") (class "Default")
      (node (ref "RUN") (pin "B") (pinfunction "B_B") (pintype "passive"))
      (node (ref "T75") (pin "3") (pinfunction "C_3") (pintype "passive"))
    )
    (net (code "234") (name "Net-(T76-C)") (class "Default")
      (node (ref "FETCH") (pin "B") (pinfunction "B_B") (pintype "passive"))
      (node (ref "T76") (pin "3") (pinfunction "C_3") (pintype "passive"))
    )
    (net (code "235") (name "Net-(T77-C)") (class "Default")
      (node (ref "EXECUTE") (pin "B") (pinfunction "B_B") (pintype "passive"))
      (node (ref "T77") (pin "3") (pinfunction "C_3") (pintype "passive"))
    )
    (net (code "236") (name "Net-(T78-C)") (class "Default")
      (node (ref "DEFER") (pin "B") (pinfunction "B_B") (pintype "passive"))
      (node (ref "T78") (pin "3") (pinfunction "C_3") (pintype "passive"))
    )
    (net (code "237") (name "Net-(T79-C)") (class "Default")
      (node (ref "T79") (pin "3") (pinfunction "C_3") (pintype "passive"))
      (node (ref "WORDCOUNT") (pin "B") (pinfunction "B_B") (pintype "passive"))
    )
    (net (code "238") (name "Net-(T80-C)") (class "Default")
      (node (ref "CURRENTADDRESS") (pin "B") (pinfunction "B_B") (pintype "passive"))
      (node (ref "T80") (pin "3") (pinfunction "C_3") (pintype "passive"))
    )
    (net (code "239") (name "Net-(T81-C)") (class "Default")
      (node (ref "BREAK") (pin "B") (pinfunction "B_B") (pintype "passive"))
      (node (ref "T81") (pin "3") (pinfunction "C_3") (pintype "passive"))
    )
    (net (code "240") (name "Net-(T82-C)") (class "Default")
      (node (ref "AND") (pin "B") (pinfunction "B_B") (pintype "passive"))
      (node (ref "T82") (pin "3") (pinfunction "C_3") (pintype "passive"))
    )
    (net (code "241") (name "Net-(T83-C)") (class "Default")
      (node (ref "T83") (pin "3") (pinfunction "C_3") (pintype "passive"))
      (node (ref "TAD") (pin "B") (pinfunction "B_B") (pintype "passive"))
    )
    (net (code "242") (name "Net-(T84-C)") (class "Default")
      (node (ref "ISZ") (pin "B") (pinfunction "B_B") (pintype "passive"))
      (node (ref "T84") (pin "3") (pinfunction "C_3") (pintype "passive"))
    )
    (net (code "243") (name "Net-(T85-C)") (class "Default")
      (node (ref "DCA") (pin "B") (pinfunction "B_B") (pintype "passive"))
      (node (ref "T85") (pin "3") (pinfunction "C_3") (pintype "passive"))
    )
    (net (code "244") (name "Net-(T86-C)") (class "Default")
      (node (ref "JMS") (pin "B") (pinfunction "B_B") (pintype "passive"))
      (node (ref "T86") (pin "3") (pinfunction "C_3") (pintype "passive"))
    )
    (net (code "245") (name "Net-(T87-C)") (class "Default")
      (node (ref "JMP") (pin "B") (pinfunction "B_B") (pintype "passive"))
      (node (ref "T87") (pin "3") (pinfunction "C_3") (pintype "passive"))
    )
    (net (code "246") (name "Net-(T88-C)") (class "Default")
      (node (ref "IOT") (pin "B") (pinfunction "B_B") (pintype "passive"))
      (node (ref "T88") (pin "3") (pinfunction "C_3") (pintype "passive"))
    )
    (net (code "247") (name "Net-(T89-C)") (class "Default")
      (node (ref "OPR") (pin "B") (pinfunction "B_B") (pintype "passive"))
      (node (ref "T89") (pin "3") (pinfunction "C_3") (pintype "passive"))
    )
    (net (code "248") (name "OPR") (class "Default")
      (node (ref "D40") (pin "16") (pinfunction "16_16") (pintype "passive"))
      (node (ref "F40BOT") (pin "11") (pinfunction "1_11") (pintype "passive"))
      (node (ref "T89") (pin "2") (pinfunction "B_2") (pintype "passive"))
    )
    (net (code "249") (name "PAUSE") (class "Default")
      (node (ref "D40") (pin "31") (pinfunction "31_31") (pintype "passive"))
      (node (ref "F40TOP") (pin "17") (pinfunction "1_17") (pintype "passive"))
      (node (ref "T74") (pin "2") (pinfunction "B_2") (pintype "passive"))
    )
    (net (code "250") (name "PC0") (class "Default")
      (node (ref "D40TOP") (pin "1") (pinfunction "1_1") (pintype "passive"))
      (node (ref "E40") (pin "1") (pinfunction "1_1") (pintype "passive"))
      (node (ref "T7") (pin "2") (pinfunction "B_2") (pintype "passive"))
    )
    (net (code "251") (name "PC1") (class "Default")
      (node (ref "D40BOT") (pin "5") (pinfunction "1_5") (pintype "passive"))
      (node (ref "E40") (pin "10") (pinfunction "10_10") (pintype "passive"))
      (node (ref "T8") (pin "2") (pinfunction "B_2") (pintype "passive"))
    )
    (net (code "252") (name "PC2") (class "Default")
      (node (ref "D40TOP") (pin "6") (pinfunction "1_6") (pintype "passive"))
      (node (ref "E40") (pin "11") (pinfunction "11_11") (pintype "passive"))
      (node (ref "T9") (pin "2") (pinfunction "B_2") (pintype "passive"))
    )
    (net (code "253") (name "PC3") (class "Default")
      (node (ref "D40BOT") (pin "14") (pinfunction "1_14") (pintype "passive"))
      (node (ref "E40") (pin "24") (pinfunction "24_24") (pintype "passive"))
      (node (ref "T10") (pin "2") (pinfunction "B_2") (pintype "passive"))
    )
    (net (code "254") (name "PC4") (class "Default")
      (node (ref "D40TOP") (pin "14") (pinfunction "1_14") (pintype "passive"))
      (node (ref "E40") (pin "25") (pinfunction "25_25") (pintype "passive"))
      (node (ref "T11") (pin "2") (pinfunction "B_2") (pintype "passive"))
    )
    (net (code "255") (name "PC5") (class "Default")
      (node (ref "D40BOT") (pin "19") (pinfunction "1_19") (pintype "passive"))
      (node (ref "E40") (pin "34") (pinfunction "34_34") (pintype "passive"))
      (node (ref "T12") (pin "2") (pinfunction "B_2") (pintype "passive"))
    )
    (net (code "256") (name "PC6") (class "Default")
      (node (ref "E40TOP") (pin "1") (pinfunction "1_1") (pintype "passive"))
      (node (ref "F40") (pin "1") (pinfunction "1_1") (pintype "passive"))
      (node (ref "T13") (pin "2") (pinfunction "B_2") (pintype "passive"))
    )
    (net (code "257") (name "PC7") (class "Default")
      (node (ref "E40BOT") (pin "5") (pinfunction "1_5") (pintype "passive"))
      (node (ref "F40") (pin "10") (pinfunction "10_10") (pintype "passive"))
      (node (ref "T14") (pin "2") (pinfunction "B_2") (pintype "passive"))
    )
    (net (code "258") (name "PC8") (class "Default")
      (node (ref "E40TOP") (pin "6") (pinfunction "1_6") (pintype "passive"))
      (node (ref "F40") (pin "11") (pinfunction "11_11") (pintype "passive"))
      (node (ref "T15") (pin "2") (pinfunction "B_2") (pintype "passive"))
    )
    (net (code "259") (name "PC9") (class "Default")
      (node (ref "E40BOT") (pin "14") (pinfunction "1_14") (pintype "passive"))
      (node (ref "F40") (pin "24") (pinfunction "24_24") (pintype "passive"))
      (node (ref "T16") (pin "2") (pinfunction "B_2") (pintype "passive"))
    )
    (net (code "260") (name "PC10") (class "Default")
      (node (ref "E40TOP") (pin "14") (pinfunction "1_14") (pintype "passive"))
      (node (ref "F40") (pin "25") (pinfunction "25_25") (pintype "passive"))
      (node (ref "T17") (pin "2") (pinfunction "B_2") (pintype "passive"))
    )
    (net (code "261") (name "PC11") (class "Default")
      (node (ref "E40BOT") (pin "19") (pinfunction "1_19") (pintype "passive"))
      (node (ref "F40") (pin "34") (pinfunction "34_34") (pintype "passive"))
      (node (ref "T18") (pin "2") (pinfunction "B_2") (pintype "passive"))
    )
    (net (code "262") (name "RUN") (class "Default")
      (node (ref "D40") (pin "33") (pinfunction "33_33") (pintype "passive"))
      (node (ref "F40TOP") (pin "18") (pinfunction "1_18") (pintype "passive"))
      (node (ref "T75") (pin "2") (pinfunction "B_2") (pintype "passive"))
    )
    (net (code "263") (name "SC0") (class "Default")
      (node (ref "C40") (pin "9") (pinfunction "9_9") (pintype "passive"))
      (node (ref "C40TOP") (pin "5") (pinfunction "1_5") (pintype "passive"))
      (node (ref "T67") (pin "2") (pinfunction "B_2") (pintype "passive"))
    )
    (net (code "264") (name "SC1") (class "Default")
      (node (ref "C40") (pin "2") (pinfunction "2_2") (pintype "passive"))
      (node (ref "C40BOT") (pin "1") (pinfunction "1_1") (pintype "passive"))
      (node (ref "T68") (pin "2") (pinfunction "B_2") (pintype "passive"))
    )
    (net (code "265") (name "SC2") (class "Default")
      (node (ref "C40") (pin "23") (pinfunction "23_23") (pintype "passive"))
      (node (ref "C40TOP") (pin "13") (pinfunction "1_13") (pintype "passive"))
      (node (ref "T69") (pin "2") (pinfunction "B_2") (pintype "passive"))
    )
    (net (code "266") (name "SC3") (class "Default")
      (node (ref "C40") (pin "12") (pinfunction "12_12") (pintype "passive"))
      (node (ref "C40BOT") (pin "6") (pinfunction "1_6") (pintype "passive"))
      (node (ref "T70") (pin "2") (pinfunction "B_2") (pintype "passive"))
    )
    (net (code "267") (name "SC4") (class "Default")
      (node (ref "C40") (pin "33") (pinfunction "33_33") (pintype "passive"))
      (node (ref "C40TOP") (pin "18") (pinfunction "1_18") (pintype "passive"))
      (node (ref "T71") (pin "2") (pinfunction "B_2") (pintype "passive"))
    )
    (net (code "268") (name "TAD") (class "Default")
      (node (ref "D40") (pin "4") (pinfunction "4_4") (pintype "passive"))
      (node (ref "F40BOT") (pin "2") (pinfunction "1_2") (pintype "passive"))
      (node (ref "T83") (pin "2") (pinfunction "B_2") (pintype "passive"))
    )
    (net (code "269") (name "WC") (class "Default")
      (node (ref "D40") (pin "30") (pinfunction "30_30") (pintype "passive"))
      (node (ref "F40BOT") (pin "17") (pinfunction "1_17") (pintype "passive"))
      (node (ref "T79") (pin "2") (pinfunction "B_2") (pintype "passive"))
    )
    (net (code "270") (name "unconnected-(C40-Pad3)") (class "Default")
      (node (ref "C40") (pin "3") (pinfunction "3_3") (pintype "passive"))
    )
    (net (code "271") (name "unconnected-(C40-Pad4)") (class "Default")
      (node (ref "C40") (pin "4") (pinfunction "4_4") (pintype "passive"))
    )
    (net (code "272") (name "unconnected-(C40-Pad5)") (class "Default")
      (node (ref "C40") (pin "5") (pinfunction "5_5") (pintype "passive"))
    )
    (net (code "273") (name "unconnected-(C40-Pad6)") (class "Default")
      (node (ref "C40") (pin "6") (pinfunction "6_6") (pintype "passive"))
    )
    (net (code "274") (name "unconnected-(C40-Pad7)") (class "Default")
      (node (ref "C40") (pin "7") (pinfunction "7_7") (pintype "passive"))
    )
    (net (code "275") (name "unconnected-(C40-Pad8)") (class "Default")
      (node (ref "C40") (pin "8") (pinfunction "8_8") (pintype "passive"))
    )
    (net (code "276") (name "unconnected-(C40-Pad13)") (class "Default")
      (node (ref "C40") (pin "13") (pinfunction "13_13") (pintype "passive"))
    )
    (net (code "277") (name "unconnected-(C40-Pad14)") (class "Default")
      (node (ref "C40") (pin "14") (pinfunction "14_14") (pintype "passive"))
    )
    (net (code "278") (name "unconnected-(C40-Pad15)") (class "Default")
      (node (ref "C40") (pin "15") (pinfunction "15_15") (pintype "passive"))
    )
    (net (code "279") (name "unconnected-(C40-Pad16)") (class "Default")
      (node (ref "C40") (pin "16") (pinfunction "16_16") (pintype "passive"))
    )
    (net (code "280") (name "unconnected-(C40-Pad21)") (class "Default")
      (node (ref "C40") (pin "21") (pinfunction "21_21") (pintype "passive"))
    )
    (net (code "281") (name "unconnected-(C40-Pad22)") (class "Default")
      (node (ref "C40") (pin "22") (pinfunction "22_22") (pintype "passive"))
    )
    (net (code "282") (name "unconnected-(C40-Pad26)") (class "Default")
      (node (ref "C40") (pin "26") (pinfunction "26_26") (pintype "passive"))
    )
    (net (code "283") (name "unconnected-(C40-Pad27)") (class "Default")
      (node (ref "C40") (pin "27") (pinfunction "27_27") (pintype "passive"))
    )
    (net (code "284") (name "unconnected-(C40-Pad29)") (class "Default")
      (node (ref "C40") (pin "29") (pinfunction "29_29") (pintype "passive"))
    )
    (net (code "285") (name "unconnected-(C40-Pad30)") (class "Default")
      (node (ref "C40") (pin "30") (pinfunction "30_30") (pintype "passive"))
    )
    (net (code "286") (name "unconnected-(C40-Pad31)") (class "Default")
      (node (ref "C40") (pin "31") (pinfunction "31_31") (pintype "passive"))
    )
    (net (code "287") (name "unconnected-(C40-Pad32)") (class "Default")
      (node (ref "C40") (pin "32") (pinfunction "32_32") (pintype "passive"))
    )
    (net (code "288") (name "unconnected-(D40-Pad1)") (class "Default")
      (node (ref "D40") (pin "1") (pinfunction "1_1") (pintype "passive"))
    )
    (net (code "289") (name "unconnected-(D40-Pad3)") (class "Default")
      (node (ref "D40") (pin "3") (pinfunction "3_3") (pintype "passive"))
    )
    (net (code "290") (name "unconnected-(D40-Pad5)") (class "Default")
      (node (ref "D40") (pin "5") (pinfunction "5_5") (pintype "passive"))
    )
    (net (code "291") (name "unconnected-(D40-Pad7)") (class "Default")
      (node (ref "D40") (pin "7") (pinfunction "7_7") (pintype "passive"))
    )
    (net (code "292") (name "unconnected-(D40-Pad9)") (class "Default")
      (node (ref "D40") (pin "9") (pinfunction "9_9") (pintype "passive"))
    )
    (net (code "293") (name "unconnected-(D40-Pad11)") (class "Default")
      (node (ref "D40") (pin "11") (pinfunction "11_11") (pintype "passive"))
    )
    (net (code "294") (name "unconnected-(D40-Pad13)") (class "Default")
      (node (ref "D40") (pin "13") (pinfunction "13_13") (pintype "passive"))
    )
    (net (code "295") (name "unconnected-(D40-Pad14)") (class "Default")
      (node (ref "D40") (pin "14") (pinfunction "14_14") (pintype "passive"))
    )
    (net (code "296") (name "unconnected-(D40-Pad15)") (class "Default")
      (node (ref "D40") (pin "15") (pinfunction "15_15") (pintype "passive"))
    )
    (net (code "297") (name "unconnected-(D40-Pad21)") (class "Default")
      (node (ref "D40") (pin "21") (pinfunction "21_21") (pintype "passive"))
    )
    (net (code "298") (name "unconnected-(D40-Pad25)") (class "Default")
      (node (ref "D40") (pin "25") (pinfunction "25_25") (pintype "passive"))
    )
    (net (code "299") (name "unconnected-(D40-Pad27)") (class "Default")
      (node (ref "D40") (pin "27") (pinfunction "27_27") (pintype "passive"))
    )
    (net (code "300") (name "unconnected-(D40-Pad29)") (class "Default")
      (node (ref "D40") (pin "29") (pinfunction "29_29") (pintype "passive"))
    )
  )
)
